# EIT_sample_circuit.net
KiCad netlist of a schematic drawn in EAGLE
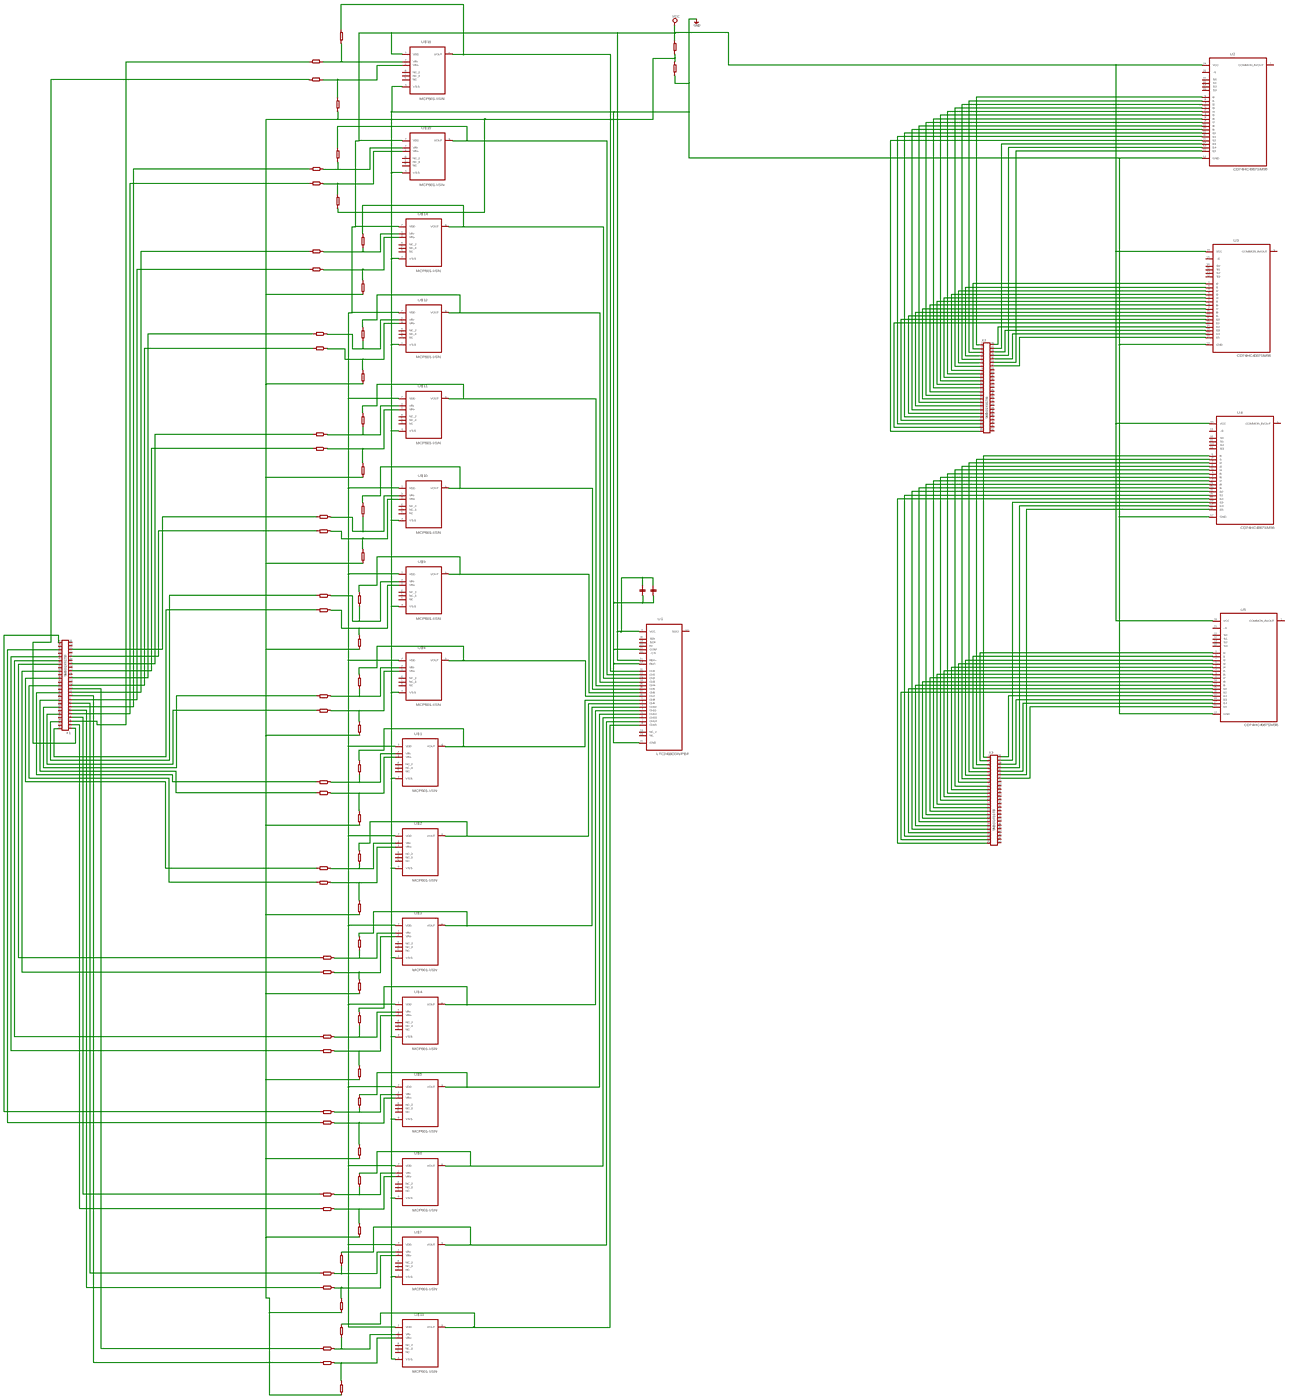
[diagram p0: schematic, sheet 1, overview]
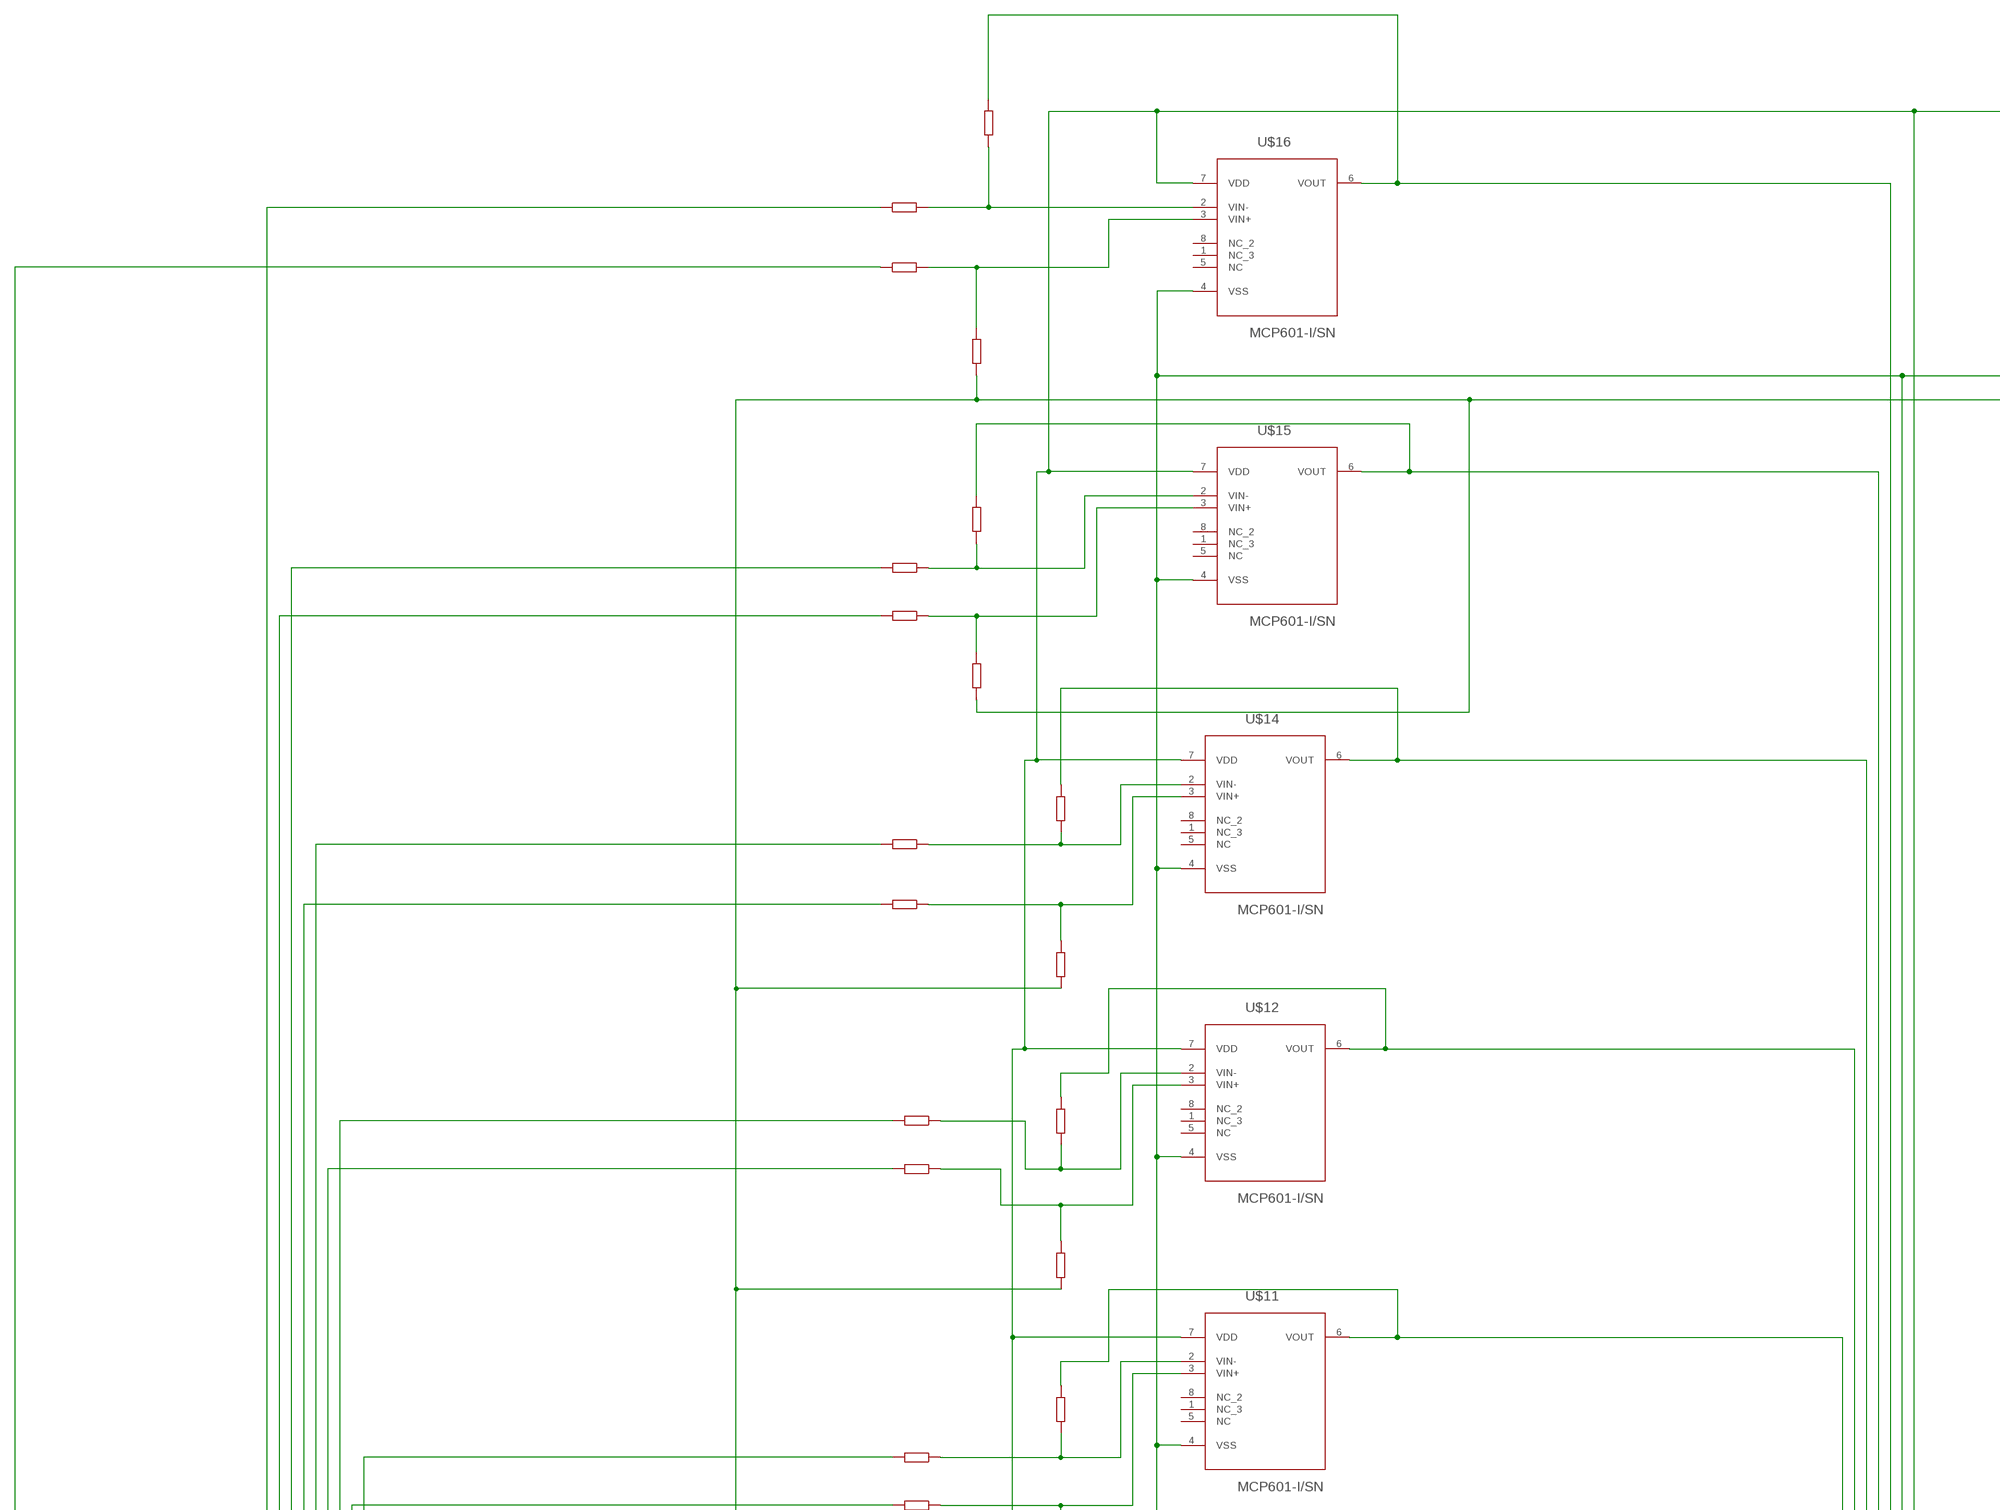
[diagram p1: schematic, sheet 1, part 1 of 5]
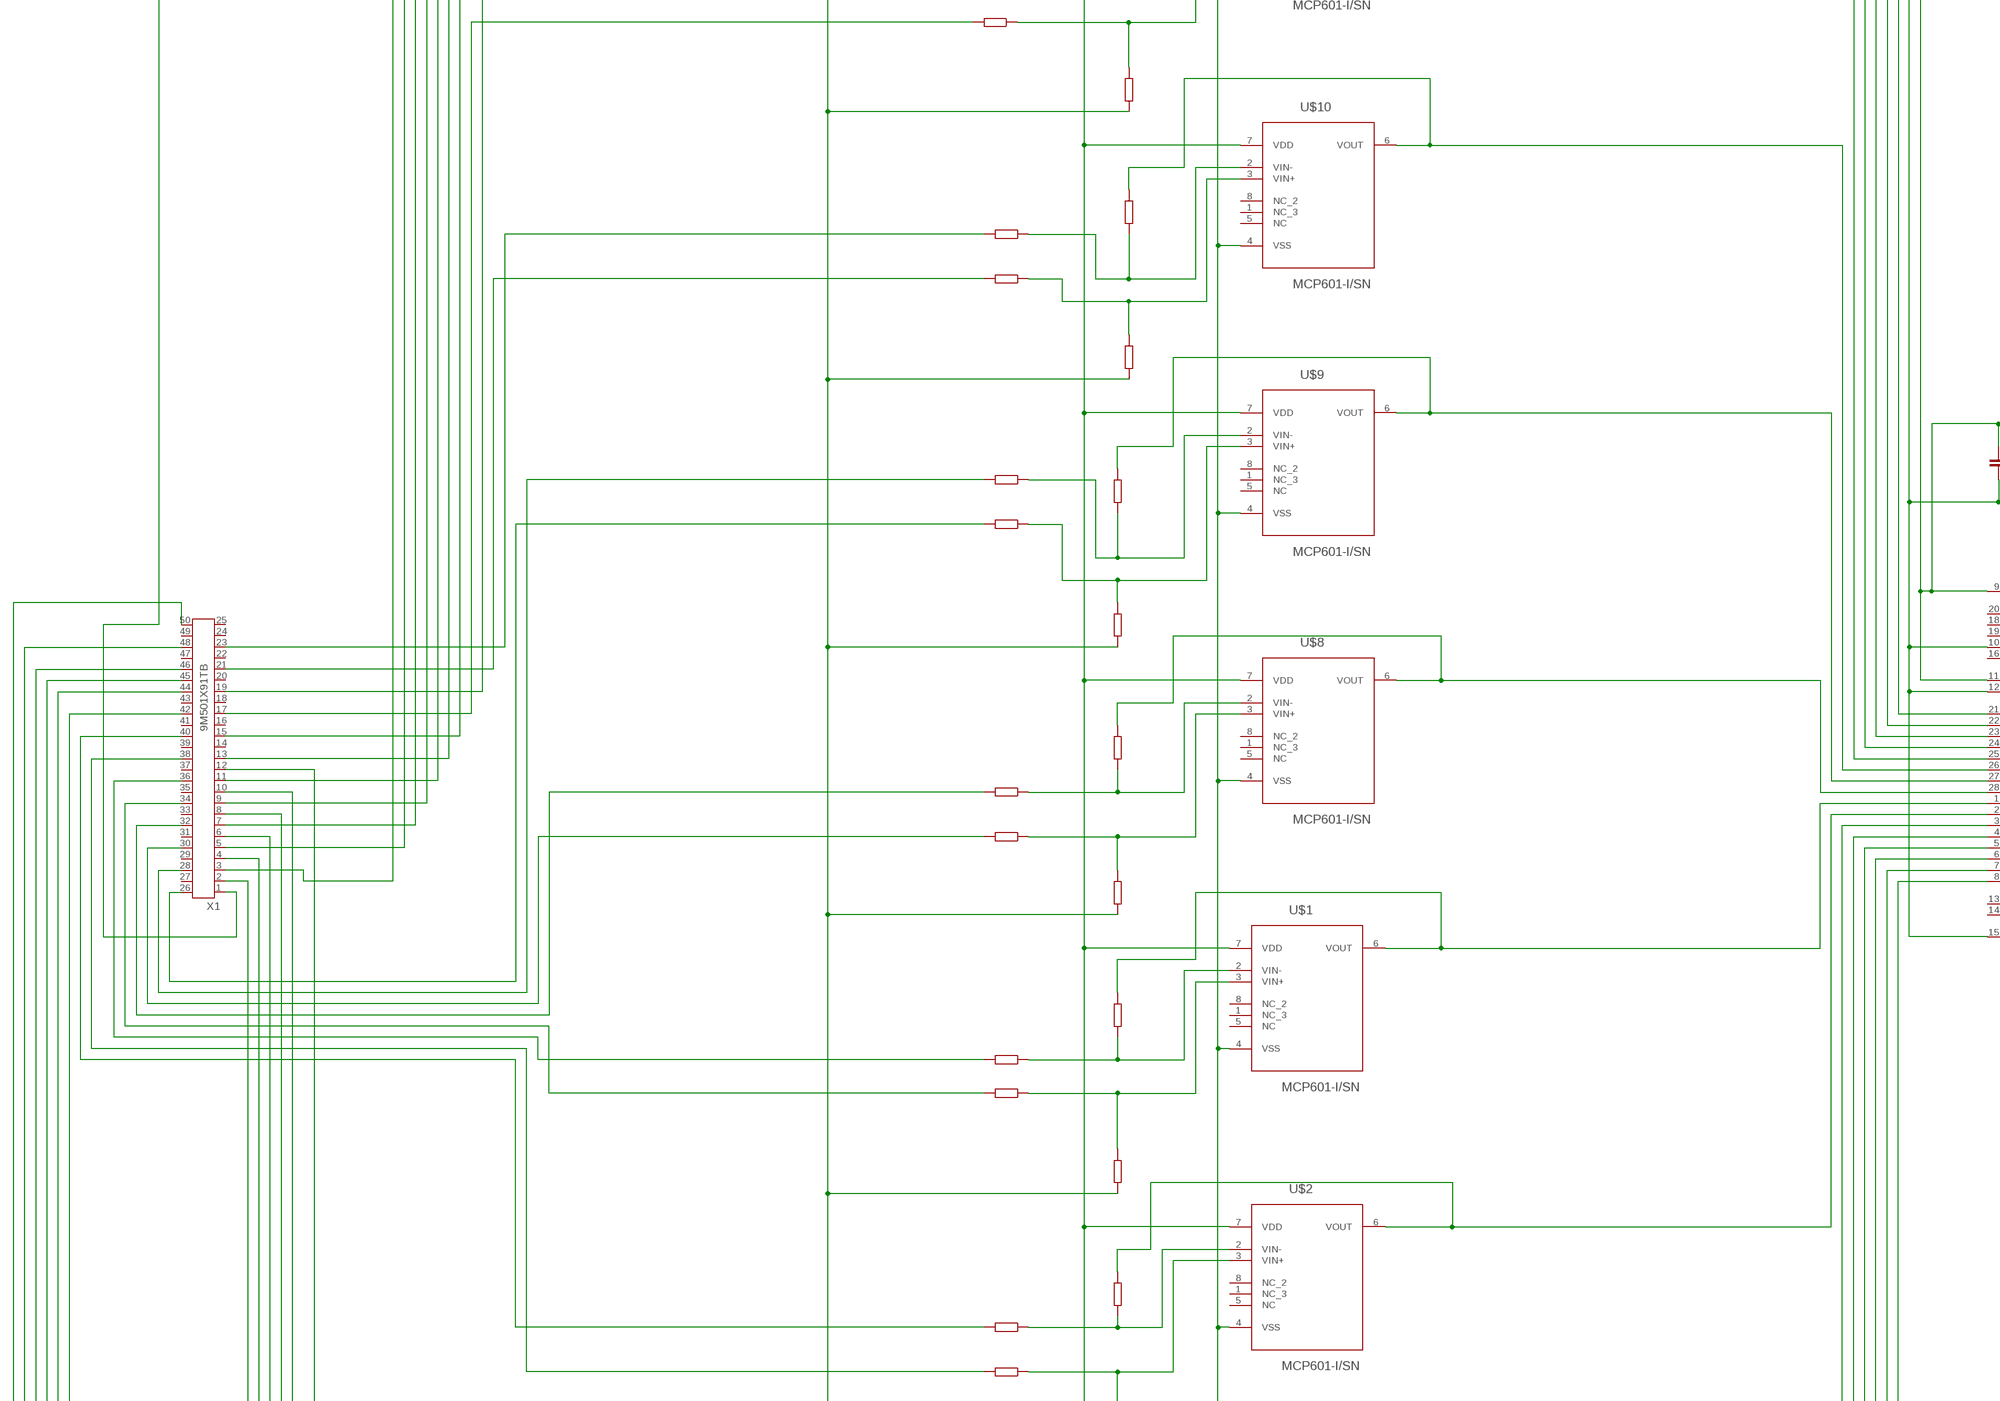
[diagram p2: schematic, sheet 1, part 2 of 5]
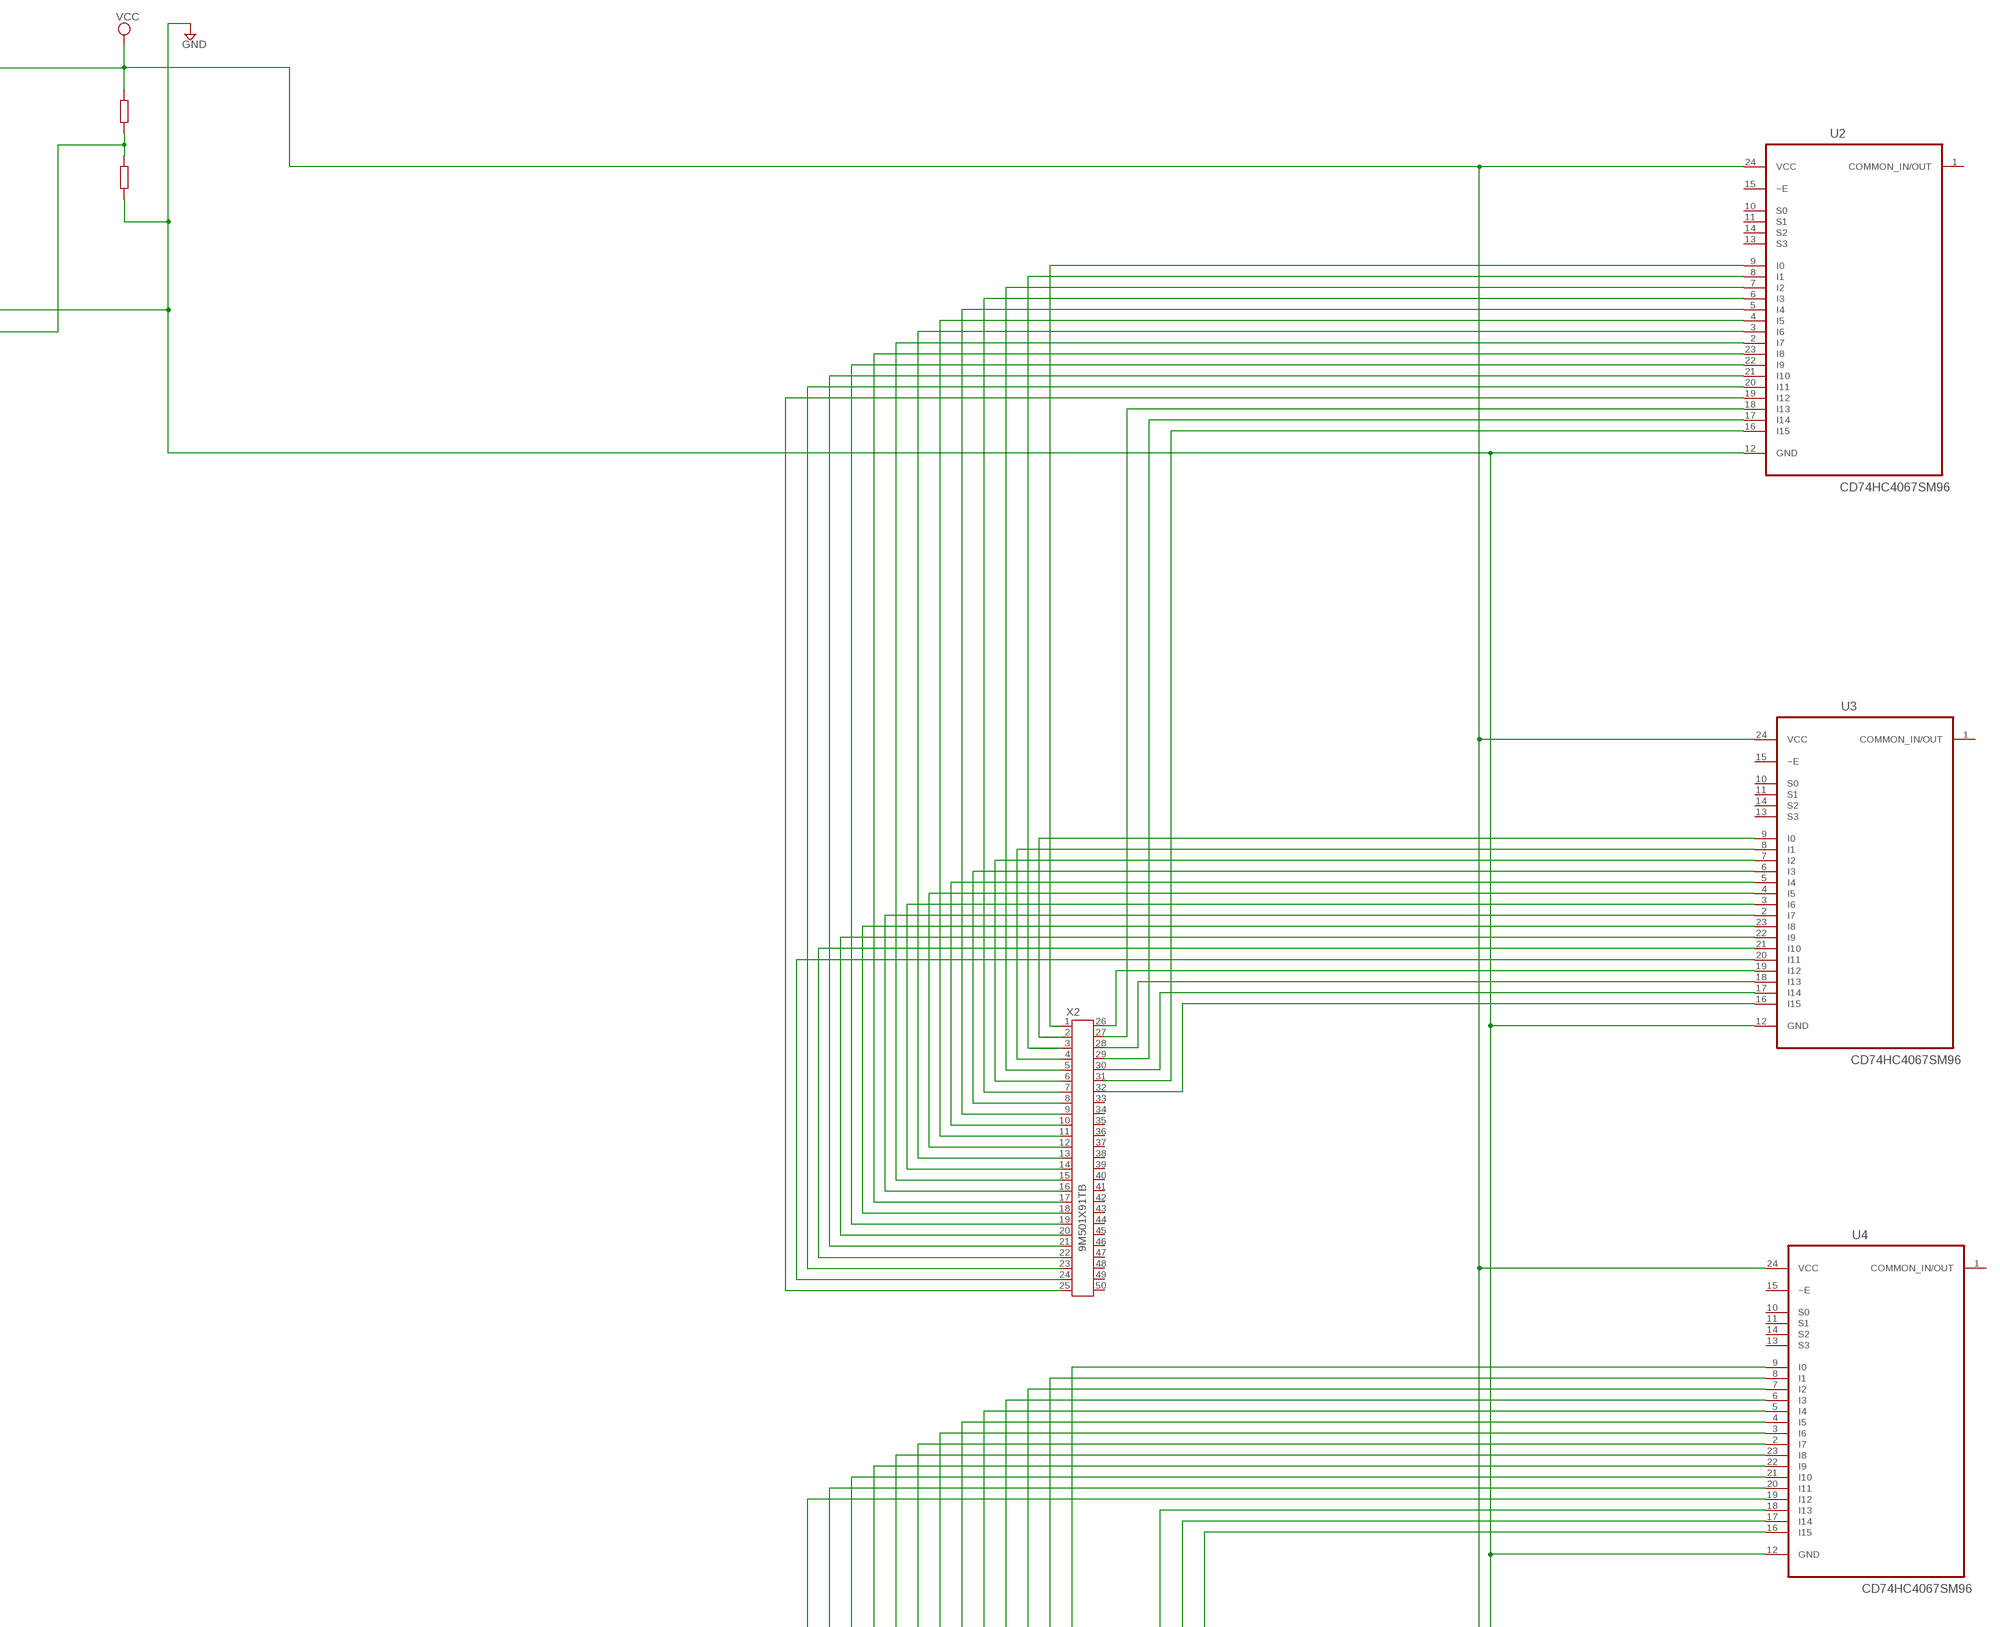
[diagram p3: schematic, sheet 1, part 3 of 5]
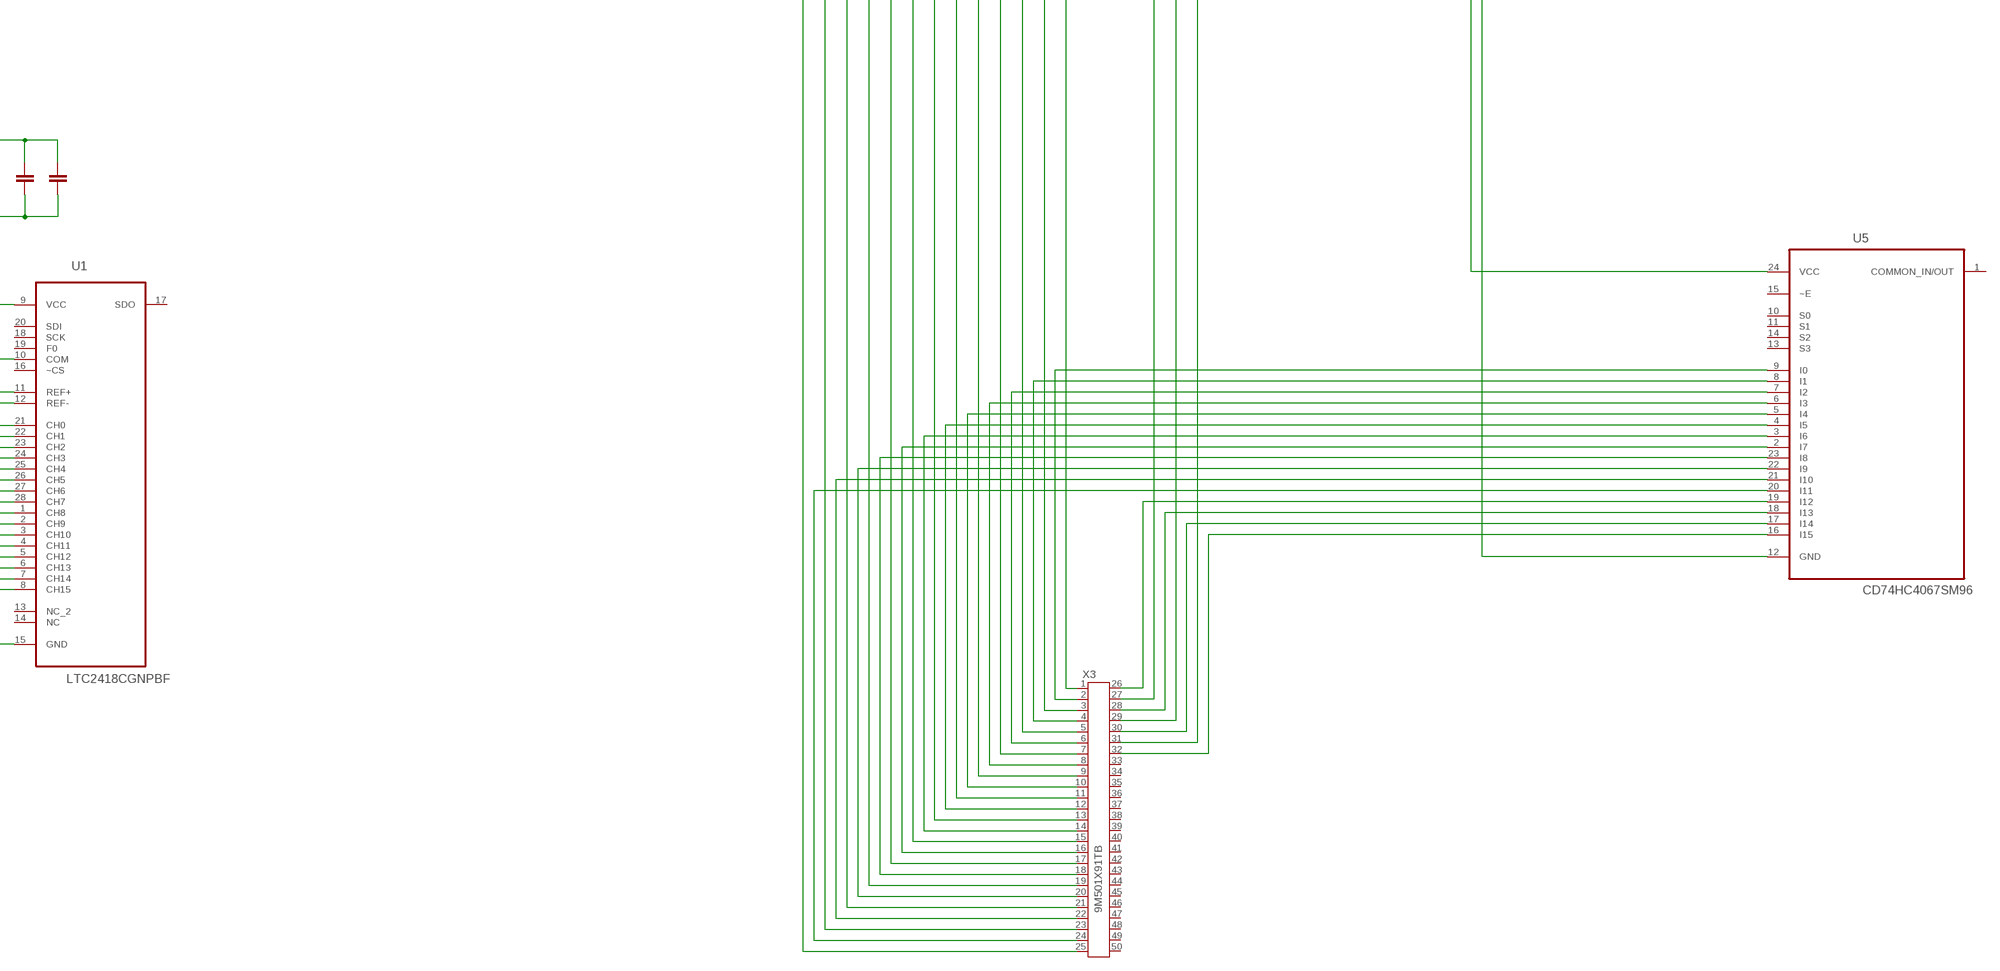
[diagram p4: schematic, sheet 1, part 4 of 5]
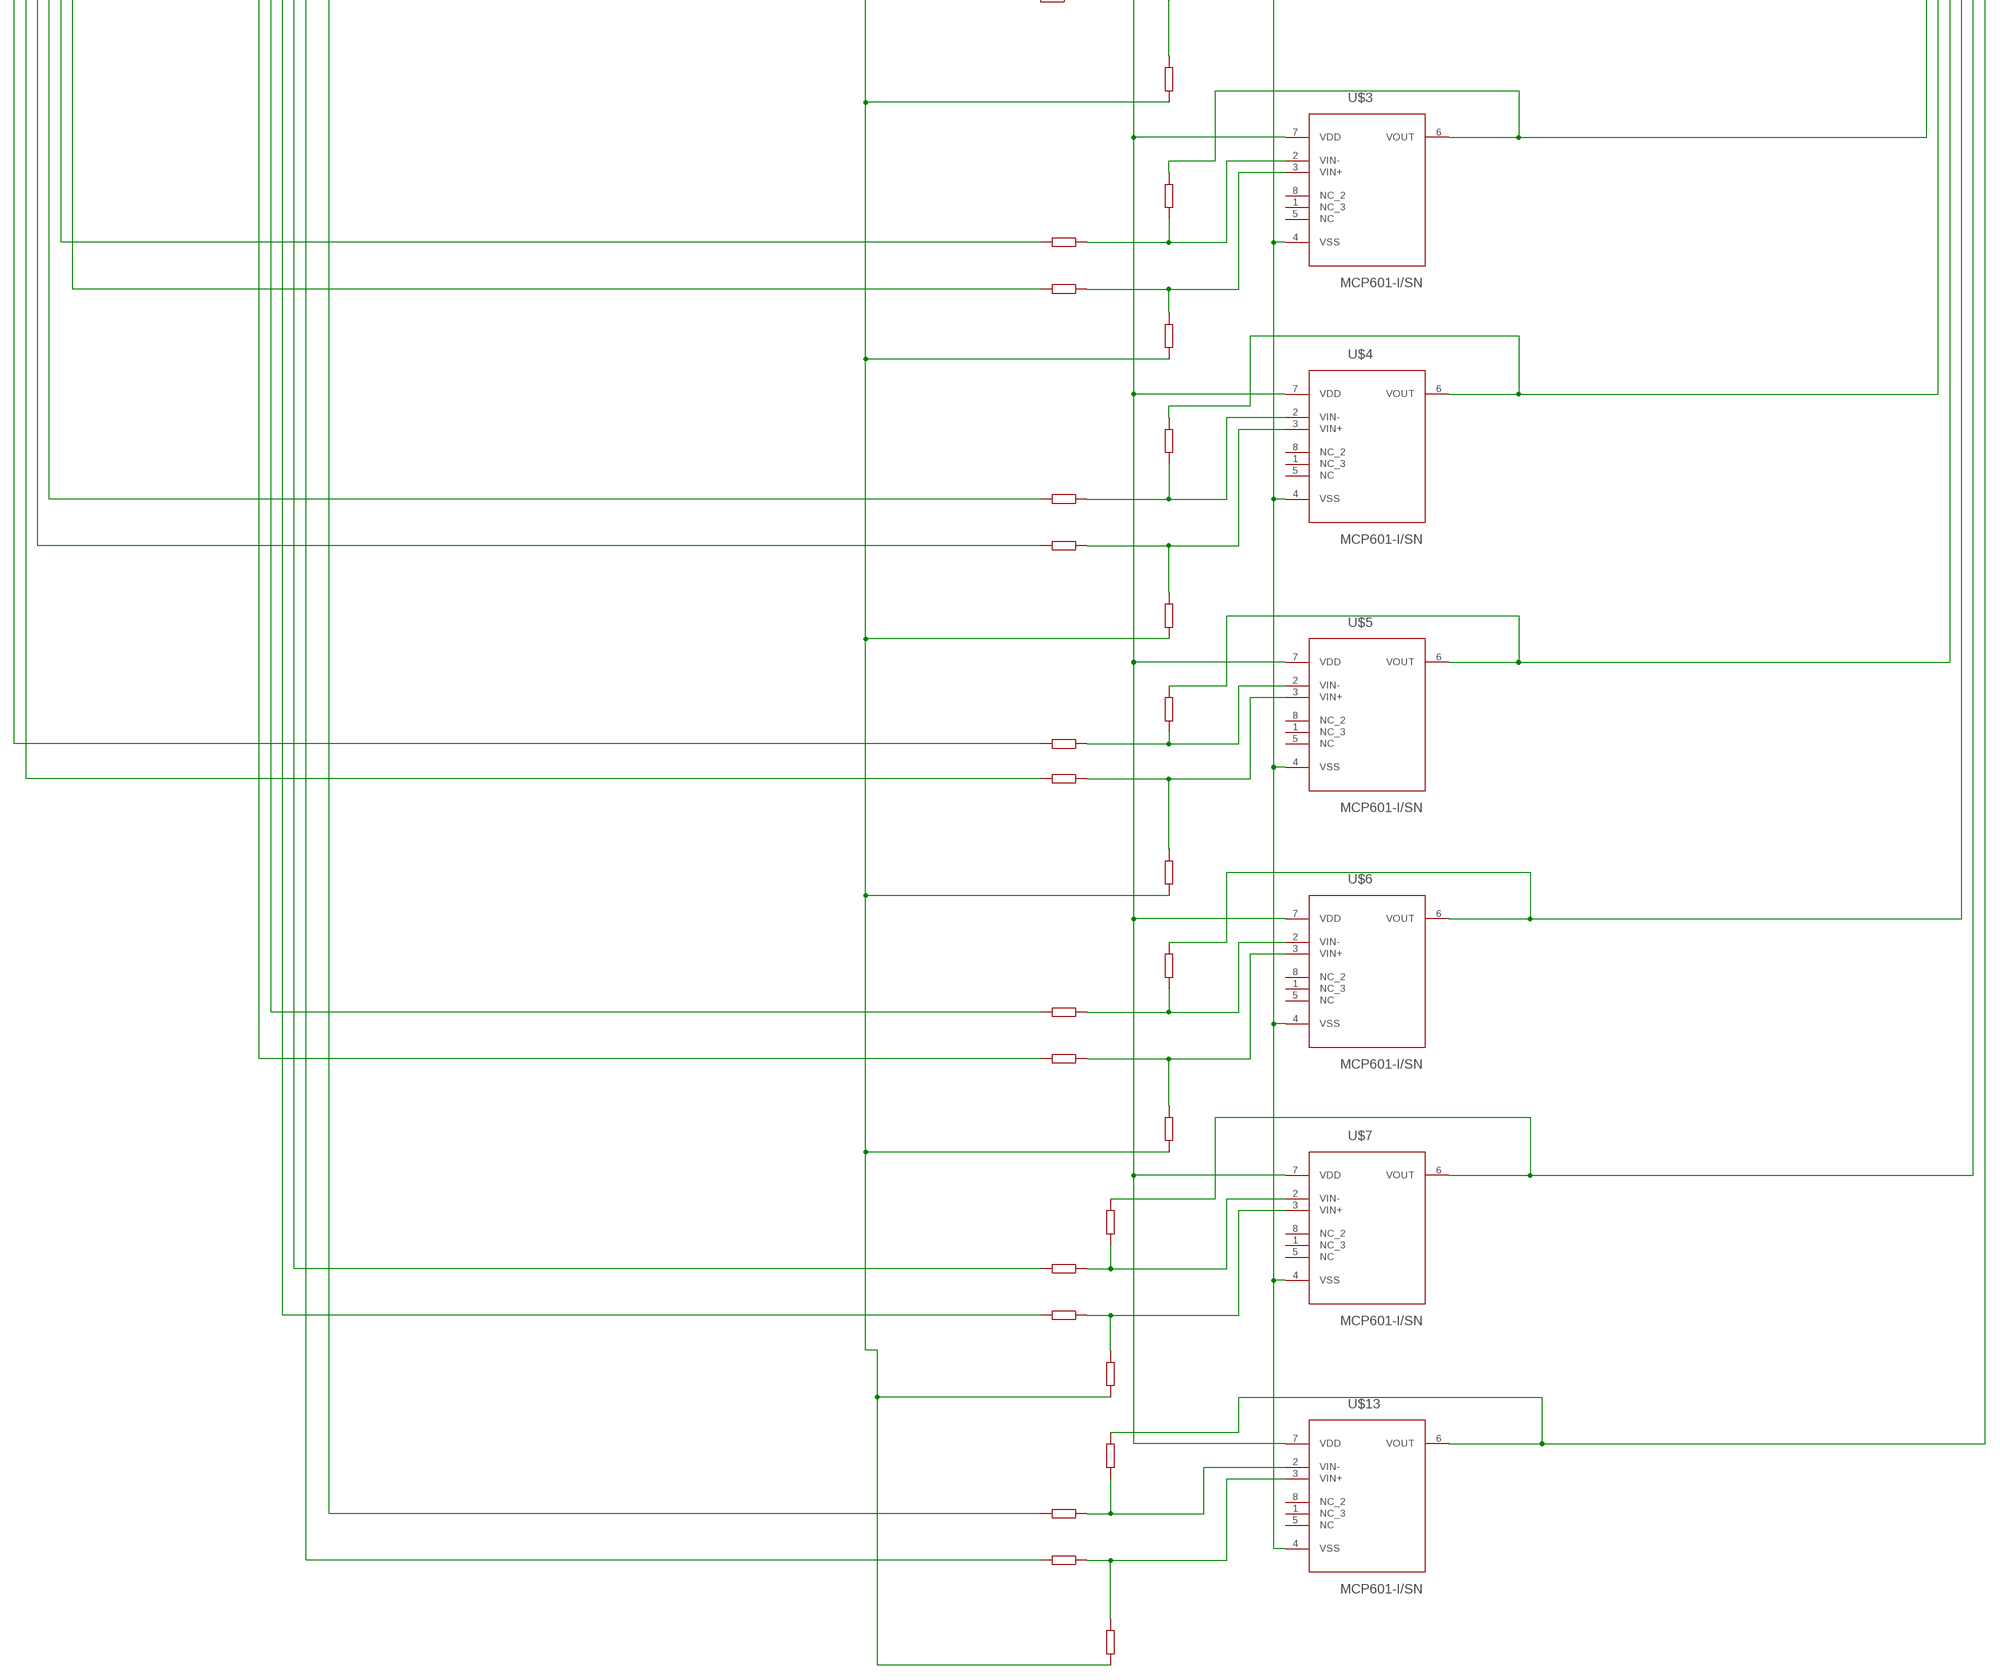
[diagram p5: schematic, sheet 1, part 5 of 5]

(export (version "E")
  (design (tool "Eeschema 10.0.6"))
  (components
    (comp (ref "U$1")
      (value "MCP601-I/SN")
      (footprint "eagle-import:SOIC127P600X175-8N")
      (libsource (lib "eagle-import") (part "MCP601-I/SN"))
    )
    (comp (ref "U$2")
      (value "MCP601-I/SN")
      (footprint "eagle-import:SOIC127P600X175-8N")
      (libsource (lib "eagle-import") (part "MCP601-I/SN"))
    )
    (comp (ref "U$3")
      (value "MCP601-I/SN")
      (footprint "eagle-import:SOIC127P600X175-8N")
      (libsource (lib "eagle-import") (part "MCP601-I/SN"))
    )
    (comp (ref "U$4")
      (value "MCP601-I/SN")
      (footprint "eagle-import:SOIC127P600X175-8N")
      (libsource (lib "eagle-import") (part "MCP601-I/SN"))
    )
    (comp (ref "U$5")
      (value "MCP601-I/SN")
      (footprint "eagle-import:SOIC127P600X175-8N")
      (libsource (lib "eagle-import") (part "MCP601-I/SN"))
    )
    (comp (ref "U$6")
      (value "MCP601-I/SN")
      (footprint "eagle-import:SOIC127P600X175-8N")
      (libsource (lib "eagle-import") (part "MCP601-I/SN"))
    )
    (comp (ref "U$7")
      (value "MCP601-I/SN")
      (footprint "eagle-import:SOIC127P600X175-8N")
      (libsource (lib "eagle-import") (part "MCP601-I/SN"))
    )
    (comp (ref "U$8")
      (value "MCP601-I/SN")
      (footprint "eagle-import:SOIC127P600X175-8N")
      (libsource (lib "eagle-import") (part "MCP601-I/SN"))
    )
    (comp (ref "U$9")
      (value "MCP601-I/SN")
      (footprint "eagle-import:SOIC127P600X175-8N")
      (libsource (lib "eagle-import") (part "MCP601-I/SN"))
    )
    (comp (ref "U$10")
      (value "MCP601-I/SN")
      (footprint "eagle-import:SOIC127P600X175-8N")
      (libsource (lib "eagle-import") (part "MCP601-I/SN"))
    )
    (comp (ref "U$11")
      (value "MCP601-I/SN")
      (footprint "eagle-import:SOIC127P600X175-8N")
      (libsource (lib "eagle-import") (part "MCP601-I/SN"))
    )
    (comp (ref "U$12")
      (value "MCP601-I/SN")
      (footprint "eagle-import:SOIC127P600X175-8N")
      (libsource (lib "eagle-import") (part "MCP601-I/SN"))
    )
    (comp (ref "U$13")
      (value "MCP601-I/SN")
      (footprint "eagle-import:SOIC127P600X175-8N")
      (libsource (lib "eagle-import") (part "MCP601-I/SN"))
    )
    (comp (ref "U$14")
      (value "MCP601-I/SN")
      (footprint "eagle-import:SOIC127P600X175-8N")
      (libsource (lib "eagle-import") (part "MCP601-I/SN"))
    )
    (comp (ref "U$15")
      (value "MCP601-I/SN")
      (footprint "eagle-import:SOIC127P600X175-8N")
      (libsource (lib "eagle-import") (part "MCP601-I/SN"))
    )
    (comp (ref "U$16")
      (value "MCP601-I/SN")
      (footprint "eagle-import:SOIC127P600X175-8N")
      (libsource (lib "eagle-import") (part "MCP601-I/SN"))
    )
    (comp (ref "U1")
      (value "LTC2418CGNPBF")
      (footprint "eagle-import:SOP63P600X175-28N")
      (fields (field (name "MPN") "LTC2418CGN#PBF"))
      (libsource (lib "eagle-import") (part "LTC2418CGNPBF"))
    )
    (comp (ref "U2")
      (value "CD74HC4067SM96")
      (footprint "eagle-import:SOP65P780X200-24N")
      (libsource (lib "eagle-import") (part "CD74HC4067SM96"))
    )
    (comp (ref "U3")
      (value "CD74HC4067SM96")
      (footprint "eagle-import:SOP65P780X200-24N")
      (libsource (lib "eagle-import") (part "CD74HC4067SM96"))
    )
    (comp (ref "U4")
      (value "CD74HC4067SM96")
      (footprint "eagle-import:SOP65P780X200-24N")
      (libsource (lib "eagle-import") (part "CD74HC4067SM96"))
    )
    (comp (ref "U5")
      (value "CD74HC4067SM96")
      (footprint "eagle-import:SOP65P780X200-24N")
      (libsource (lib "eagle-import") (part "CD74HC4067SM96"))
    )
    (comp (ref "X1")
      (value "9M501X91TB")
      (footprint "eagle-import:9M501X91")
      (libsource (lib "eagle-import") (part "9M501X91TB"))
    )
    (comp (ref "X2")
      (value "9M501X91TB")
      (footprint "eagle-import:9M501X91")
      (libsource (lib "eagle-import") (part "9M501X91TB"))
    )
    (comp (ref "X3")
      (value "9M501X91TB")
      (footprint "eagle-import:9M501X91")
      (libsource (lib "eagle-import") (part "9M501X91TB"))
    )
  )
  (nets
    (net (code "1") (name "GND") (class "Default")
      (node (ref "U$1") (pin "4") (pinfunction "VSS_4") (pintype "power_in"))
      (node (ref "U$10") (pin "4") (pinfunction "VSS_4") (pintype "power_in"))
      (node (ref "U$11") (pin "4") (pinfunction "VSS_4") (pintype "power_in"))
      (node (ref "U$12") (pin "4") (pinfunction "VSS_4") (pintype "power_in"))
      (node (ref "U$13") (pin "4") (pinfunction "VSS_4") (pintype "power_in"))
      (node (ref "U$14") (pin "4") (pinfunction "VSS_4") (pintype "power_in"))
      (node (ref "U$15") (pin "4") (pinfunction "VSS_4") (pintype "power_in"))
      (node (ref "U$16") (pin "4") (pinfunction "VSS_4") (pintype "power_in"))
      (node (ref "U$2") (pin "4") (pinfunction "VSS_4") (pintype "power_in"))
      (node (ref "U$3") (pin "4") (pinfunction "VSS_4") (pintype "power_in"))
      (node (ref "U$4") (pin "4") (pinfunction "VSS_4") (pintype "power_in"))
      (node (ref "U$5") (pin "4") (pinfunction "VSS_4") (pintype "power_in"))
      (node (ref "U$6") (pin "4") (pinfunction "VSS_4") (pintype "power_in"))
      (node (ref "U$7") (pin "4") (pinfunction "VSS_4") (pintype "power_in"))
      (node (ref "U$8") (pin "4") (pinfunction "VSS_4") (pintype "power_in"))
      (node (ref "U$9") (pin "4") (pinfunction "VSS_4") (pintype "power_in"))
      (node (ref "U1") (pin "10") (pinfunction "COM_10") (pintype "input"))
      (node (ref "U1") (pin "12") (pinfunction "REF-_12") (pintype "input"))
      (node (ref "U1") (pin "15") (pinfunction "GND_15") (pintype "passive"))
      (node (ref "U2") (pin "12") (pinfunction "GND_12") (pintype "passive"))
      (node (ref "U3") (pin "12") (pinfunction "GND_12") (pintype "passive"))
      (node (ref "U4") (pin "12") (pinfunction "GND_12") (pintype "passive"))
      (node (ref "U5") (pin "12") (pinfunction "GND_12") (pintype "passive"))
    )
    (net (code "2") (name "Net-(U$1-VOUT)") (class "Default")
      (node (ref "U$1") (pin "6") (pinfunction "VOUT_6") (pintype "output"))
      (node (ref "U1") (pin "1") (pinfunction "CH8_1") (pintype "input"))
    )
    (net (code "3") (name "Net-(U$2-VOUT)") (class "Default")
      (node (ref "U$2") (pin "6") (pinfunction "VOUT_6") (pintype "output"))
      (node (ref "U1") (pin "2") (pinfunction "CH9_2") (pintype "input"))
    )
    (net (code "4") (name "Net-(U$3-VOUT)") (class "Default")
      (node (ref "U$3") (pin "6") (pinfunction "VOUT_6") (pintype "output"))
      (node (ref "U1") (pin "3") (pinfunction "CH10_3") (pintype "input"))
    )
    (net (code "5") (name "Net-(U$4-VOUT)") (class "Default")
      (node (ref "U$4") (pin "6") (pinfunction "VOUT_6") (pintype "output"))
      (node (ref "U1") (pin "4") (pinfunction "CH11_4") (pintype "input"))
    )
    (net (code "6") (name "Net-(U$5-VOUT)") (class "Default")
      (node (ref "U$5") (pin "6") (pinfunction "VOUT_6") (pintype "output"))
      (node (ref "U1") (pin "5") (pinfunction "CH12_5") (pintype "input"))
    )
    (net (code "7") (name "Net-(U$6-VOUT)") (class "Default")
      (node (ref "U$6") (pin "6") (pinfunction "VOUT_6") (pintype "output"))
      (node (ref "U1") (pin "6") (pinfunction "CH13_6") (pintype "input"))
    )
    (net (code "8") (name "Net-(U$7-VOUT)") (class "Default")
      (node (ref "U$7") (pin "6") (pinfunction "VOUT_6") (pintype "output"))
      (node (ref "U1") (pin "7") (pinfunction "CH14_7") (pintype "input"))
    )
    (net (code "9") (name "Net-(U$8-VOUT)") (class "Default")
      (node (ref "U$8") (pin "6") (pinfunction "VOUT_6") (pintype "output"))
      (node (ref "U1") (pin "28") (pinfunction "CH7_28") (pintype "input"))
    )
    (net (code "10") (name "Net-(U$9-VOUT)") (class "Default")
      (node (ref "U$9") (pin "6") (pinfunction "VOUT_6") (pintype "output"))
      (node (ref "U1") (pin "27") (pinfunction "CH6_27") (pintype "input"))
    )
    (net (code "11") (name "Net-(U$10-VOUT)") (class "Default")
      (node (ref "U$10") (pin "6") (pinfunction "VOUT_6") (pintype "output"))
      (node (ref "U1") (pin "26") (pinfunction "CH5_26") (pintype "input"))
    )
    (net (code "12") (name "Net-(U$11-VOUT)") (class "Default")
      (node (ref "U$11") (pin "6") (pinfunction "VOUT_6") (pintype "output"))
      (node (ref "U1") (pin "25") (pinfunction "CH4_25") (pintype "input"))
    )
    (net (code "13") (name "Net-(U$12-VOUT)") (class "Default")
      (node (ref "U$12") (pin "6") (pinfunction "VOUT_6") (pintype "output"))
      (node (ref "U1") (pin "24") (pinfunction "CH3_24") (pintype "input"))
    )
    (net (code "14") (name "Net-(U$13-VOUT)") (class "Default")
      (node (ref "U$13") (pin "6") (pinfunction "VOUT_6") (pintype "output"))
      (node (ref "U1") (pin "8") (pinfunction "CH15_8") (pintype "input"))
    )
    (net (code "15") (name "Net-(U$14-VOUT)") (class "Default")
      (node (ref "U$14") (pin "6") (pinfunction "VOUT_6") (pintype "output"))
      (node (ref "U1") (pin "23") (pinfunction "CH2_23") (pintype "input"))
    )
    (net (code "16") (name "Net-(U$15-VOUT)") (class "Default")
      (node (ref "U$15") (pin "6") (pinfunction "VOUT_6") (pintype "output"))
      (node (ref "U1") (pin "22") (pinfunction "CH1_22") (pintype "input"))
    )
    (net (code "17") (name "Net-(U$16-VOUT)") (class "Default")
      (node (ref "U$16") (pin "6") (pinfunction "VOUT_6") (pintype "output"))
      (node (ref "U1") (pin "21") (pinfunction "CH0_21") (pintype "input"))
    )
    (net (code "18") (name "Net-(U2-I0)") (class "Default")
      (node (ref "U2") (pin "9") (pinfunction "I0_9") (pintype "input"))
      (node (ref "X2") (pin "1") (pinfunction "1_1") (pintype "passive"))
    )
    (net (code "19") (name "Net-(U2-I1)") (class "Default")
      (node (ref "U2") (pin "8") (pinfunction "I1_8") (pintype "input"))
      (node (ref "X2") (pin "3") (pinfunction "3_3") (pintype "passive"))
    )
    (net (code "20") (name "Net-(U2-I2)") (class "Default")
      (node (ref "U2") (pin "7") (pinfunction "I2_7") (pintype "input"))
      (node (ref "X2") (pin "5") (pinfunction "5_5") (pintype "passive"))
    )
    (net (code "21") (name "Net-(U2-I3)") (class "Default")
      (node (ref "U2") (pin "6") (pinfunction "I3_6") (pintype "input"))
      (node (ref "X2") (pin "7") (pinfunction "7_7") (pintype "passive"))
    )
    (net (code "22") (name "Net-(U2-I4)") (class "Default")
      (node (ref "U2") (pin "5") (pinfunction "I4_5") (pintype "input"))
      (node (ref "X2") (pin "9") (pinfunction "9_9") (pintype "passive"))
    )
    (net (code "23") (name "Net-(U2-I5)") (class "Default")
      (node (ref "U2") (pin "4") (pinfunction "I5_4") (pintype "input"))
      (node (ref "X2") (pin "11") (pinfunction "11_11") (pintype "passive"))
    )
    (net (code "24") (name "Net-(U2-I6)") (class "Default")
      (node (ref "U2") (pin "3") (pinfunction "I6_3") (pintype "input"))
      (node (ref "X2") (pin "13") (pinfunction "13_13") (pintype "passive"))
    )
    (net (code "25") (name "Net-(U2-I7)") (class "Default")
      (node (ref "U2") (pin "2") (pinfunction "I7_2") (pintype "input"))
      (node (ref "X2") (pin "15") (pinfunction "15_15") (pintype "passive"))
    )
    (net (code "26") (name "Net-(U2-I8)") (class "Default")
      (node (ref "U2") (pin "23") (pinfunction "I8_23") (pintype "input"))
      (node (ref "X2") (pin "17") (pinfunction "17_17") (pintype "passive"))
    )
    (net (code "27") (name "Net-(U2-I9)") (class "Default")
      (node (ref "U2") (pin "22") (pinfunction "I9_22") (pintype "input"))
      (node (ref "X2") (pin "19") (pinfunction "19_19") (pintype "passive"))
    )
    (net (code "28") (name "Net-(U2-I10)") (class "Default")
      (node (ref "U2") (pin "21") (pinfunction "I10_21") (pintype "input"))
      (node (ref "X2") (pin "21") (pinfunction "21_21") (pintype "passive"))
    )
    (net (code "29") (name "Net-(U2-I11)") (class "Default")
      (node (ref "U2") (pin "20") (pinfunction "I11_20") (pintype "input"))
      (node (ref "X2") (pin "23") (pinfunction "23_23") (pintype "passive"))
    )
    (net (code "30") (name "Net-(U2-I12)") (class "Default")
      (node (ref "U2") (pin "19") (pinfunction "I12_19") (pintype "input"))
      (node (ref "X2") (pin "25") (pinfunction "25_25") (pintype "passive"))
    )
    (net (code "31") (name "Net-(U2-I13)") (class "Default")
      (node (ref "U2") (pin "18") (pinfunction "I13_18") (pintype "input"))
      (node (ref "X2") (pin "27") (pinfunction "27_27") (pintype "passive"))
    )
    (net (code "32") (name "Net-(U2-I14)") (class "Default")
      (node (ref "U2") (pin "17") (pinfunction "I14_17") (pintype "input"))
      (node (ref "X2") (pin "29") (pinfunction "29_29") (pintype "passive"))
    )
    (net (code "33") (name "Net-(U2-I15)") (class "Default")
      (node (ref "U2") (pin "16") (pinfunction "I15_16") (pintype "input"))
      (node (ref "X2") (pin "31") (pinfunction "31_31") (pintype "passive"))
    )
    (net (code "34") (name "Net-(U3-I0)") (class "Default")
      (node (ref "U3") (pin "9") (pinfunction "I0_9") (pintype "input"))
      (node (ref "X2") (pin "2") (pinfunction "2_2") (pintype "passive"))
    )
    (net (code "35") (name "Net-(U3-I1)") (class "Default")
      (node (ref "U3") (pin "8") (pinfunction "I1_8") (pintype "input"))
      (node (ref "X2") (pin "4") (pinfunction "4_4") (pintype "passive"))
    )
    (net (code "36") (name "Net-(U3-I2)") (class "Default")
      (node (ref "U3") (pin "7") (pinfunction "I2_7") (pintype "input"))
      (node (ref "X2") (pin "6") (pinfunction "6_6") (pintype "passive"))
    )
    (net (code "37") (name "Net-(U3-I3)") (class "Default")
      (node (ref "U3") (pin "6") (pinfunction "I3_6") (pintype "input"))
      (node (ref "X2") (pin "8") (pinfunction "8_8") (pintype "passive"))
    )
    (net (code "38") (name "Net-(U3-I4)") (class "Default")
      (node (ref "U3") (pin "5") (pinfunction "I4_5") (pintype "input"))
      (node (ref "X2") (pin "10") (pinfunction "10_10") (pintype "passive"))
    )
    (net (code "39") (name "Net-(U3-I5)") (class "Default")
      (node (ref "U3") (pin "4") (pinfunction "I5_4") (pintype "input"))
      (node (ref "X2") (pin "12") (pinfunction "12_12") (pintype "passive"))
    )
    (net (code "40") (name "Net-(U3-I6)") (class "Default")
      (node (ref "U3") (pin "3") (pinfunction "I6_3") (pintype "input"))
      (node (ref "X2") (pin "14") (pinfunction "14_14") (pintype "passive"))
    )
    (net (code "41") (name "Net-(U3-I7)") (class "Default")
      (node (ref "U3") (pin "2") (pinfunction "I7_2") (pintype "input"))
      (node (ref "X2") (pin "16") (pinfunction "16_16") (pintype "passive"))
    )
    (net (code "42") (name "Net-(U3-I8)") (class "Default")
      (node (ref "U3") (pin "23") (pinfunction "I8_23") (pintype "input"))
      (node (ref "X2") (pin "18") (pinfunction "18_18") (pintype "passive"))
    )
    (net (code "43") (name "Net-(U3-I9)") (class "Default")
      (node (ref "U3") (pin "22") (pinfunction "I9_22") (pintype "input"))
      (node (ref "X2") (pin "20") (pinfunction "20_20") (pintype "passive"))
    )
    (net (code "44") (name "Net-(U3-I10)") (class "Default")
      (node (ref "U3") (pin "21") (pinfunction "I10_21") (pintype "input"))
      (node (ref "X2") (pin "22") (pinfunction "22_22") (pintype "passive"))
    )
    (net (code "45") (name "Net-(U3-I11)") (class "Default")
      (node (ref "U3") (pin "20") (pinfunction "I11_20") (pintype "input"))
      (node (ref "X2") (pin "24") (pinfunction "24_24") (pintype "passive"))
    )
    (net (code "46") (name "Net-(U3-I12)") (class "Default")
      (node (ref "U3") (pin "19") (pinfunction "I12_19") (pintype "input"))
      (node (ref "X2") (pin "26") (pinfunction "26_26") (pintype "passive"))
    )
    (net (code "47") (name "Net-(U3-I13)") (class "Default")
      (node (ref "U3") (pin "18") (pinfunction "I13_18") (pintype "input"))
      (node (ref "X2") (pin "28") (pinfunction "28_28") (pintype "passive"))
    )
    (net (code "48") (name "Net-(U3-I14)") (class "Default")
      (node (ref "U3") (pin "17") (pinfunction "I14_17") (pintype "input"))
      (node (ref "X2") (pin "30") (pinfunction "30_30") (pintype "passive"))
    )
    (net (code "49") (name "Net-(U3-I15)") (class "Default")
      (node (ref "U3") (pin "16") (pinfunction "I15_16") (pintype "input"))
      (node (ref "X2") (pin "32") (pinfunction "32_32") (pintype "passive"))
    )
    (net (code "50") (name "Net-(U4-I0)") (class "Default")
      (node (ref "U4") (pin "9") (pinfunction "I0_9") (pintype "input"))
      (node (ref "X3") (pin "1") (pinfunction "1_1") (pintype "passive"))
    )
    (net (code "51") (name "Net-(U4-I1)") (class "Default")
      (node (ref "U4") (pin "8") (pinfunction "I1_8") (pintype "input"))
      (node (ref "X3") (pin "3") (pinfunction "3_3") (pintype "passive"))
    )
    (net (code "52") (name "Net-(U4-I2)") (class "Default")
      (node (ref "U4") (pin "7") (pinfunction "I2_7") (pintype "input"))
      (node (ref "X3") (pin "5") (pinfunction "5_5") (pintype "passive"))
    )
    (net (code "53") (name "Net-(U4-I3)") (class "Default")
      (node (ref "U4") (pin "6") (pinfunction "I3_6") (pintype "input"))
      (node (ref "X3") (pin "7") (pinfunction "7_7") (pintype "passive"))
    )
    (net (code "54") (name "Net-(U4-I4)") (class "Default")
      (node (ref "U4") (pin "5") (pinfunction "I4_5") (pintype "input"))
      (node (ref "X3") (pin "9") (pinfunction "9_9") (pintype "passive"))
    )
    (net (code "55") (name "Net-(U4-I5)") (class "Default")
      (node (ref "U4") (pin "4") (pinfunction "I5_4") (pintype "input"))
      (node (ref "X3") (pin "11") (pinfunction "11_11") (pintype "passive"))
    )
    (net (code "56") (name "Net-(U4-I6)") (class "Default")
      (node (ref "U4") (pin "3") (pinfunction "I6_3") (pintype "input"))
      (node (ref "X3") (pin "13") (pinfunction "13_13") (pintype "passive"))
    )
    (net (code "57") (name "Net-(U4-I7)") (class "Default")
      (node (ref "U4") (pin "2") (pinfunction "I7_2") (pintype "input"))
      (node (ref "X3") (pin "15") (pinfunction "15_15") (pintype "passive"))
    )
    (net (code "58") (name "Net-(U4-I8)") (class "Default")
      (node (ref "U4") (pin "23") (pinfunction "I8_23") (pintype "input"))
      (node (ref "X3") (pin "17") (pinfunction "17_17") (pintype "passive"))
    )
    (net (code "59") (name "Net-(U4-I9)") (class "Default")
      (node (ref "U4") (pin "22") (pinfunction "I9_22") (pintype "input"))
      (node (ref "X3") (pin "19") (pinfunction "19_19") (pintype "passive"))
    )
    (net (code "60") (name "Net-(U4-I10)") (class "Default")
      (node (ref "U4") (pin "21") (pinfunction "I10_21") (pintype "input"))
      (node (ref "X3") (pin "21") (pinfunction "21_21") (pintype "passive"))
    )
    (net (code "61") (name "Net-(U4-I11)") (class "Default")
      (node (ref "U4") (pin "20") (pinfunction "I11_20") (pintype "input"))
      (node (ref "X3") (pin "23") (pinfunction "23_23") (pintype "passive"))
    )
    (net (code "62") (name "Net-(U4-I12)") (class "Default")
      (node (ref "U4") (pin "19") (pinfunction "I12_19") (pintype "input"))
      (node (ref "X3") (pin "25") (pinfunction "25_25") (pintype "passive"))
    )
    (net (code "63") (name "Net-(U4-I13)") (class "Default")
      (node (ref "U4") (pin "18") (pinfunction "I13_18") (pintype "input"))
      (node (ref "X3") (pin "27") (pinfunction "27_27") (pintype "passive"))
    )
    (net (code "64") (name "Net-(U4-I14)") (class "Default")
      (node (ref "U4") (pin "17") (pinfunction "I14_17") (pintype "input"))
      (node (ref "X3") (pin "29") (pinfunction "29_29") (pintype "passive"))
    )
    (net (code "65") (name "Net-(U4-I15)") (class "Default")
      (node (ref "U4") (pin "16") (pinfunction "I15_16") (pintype "input"))
      (node (ref "X3") (pin "31") (pinfunction "31_31") (pintype "passive"))
    )
    (net (code "66") (name "Net-(U5-I0)") (class "Default")
      (node (ref "U5") (pin "9") (pinfunction "I0_9") (pintype "input"))
      (node (ref "X3") (pin "2") (pinfunction "2_2") (pintype "passive"))
    )
    (net (code "67") (name "Net-(U5-I1)") (class "Default")
      (node (ref "U5") (pin "8") (pinfunction "I1_8") (pintype "input"))
      (node (ref "X3") (pin "4") (pinfunction "4_4") (pintype "passive"))
    )
    (net (code "68") (name "Net-(U5-I2)") (class "Default")
      (node (ref "U5") (pin "7") (pinfunction "I2_7") (pintype "input"))
      (node (ref "X3") (pin "6") (pinfunction "6_6") (pintype "passive"))
    )
    (net (code "69") (name "Net-(U5-I3)") (class "Default")
      (node (ref "U5") (pin "6") (pinfunction "I3_6") (pintype "input"))
      (node (ref "X3") (pin "8") (pinfunction "8_8") (pintype "passive"))
    )
    (net (code "70") (name "Net-(U5-I4)") (class "Default")
      (node (ref "U5") (pin "5") (pinfunction "I4_5") (pintype "input"))
      (node (ref "X3") (pin "10") (pinfunction "10_10") (pintype "passive"))
    )
    (net (code "71") (name "Net-(U5-I5)") (class "Default")
      (node (ref "U5") (pin "4") (pinfunction "I5_4") (pintype "input"))
      (node (ref "X3") (pin "12") (pinfunction "12_12") (pintype "passive"))
    )
    (net (code "72") (name "Net-(U5-I6)") (class "Default")
      (node (ref "U5") (pin "3") (pinfunction "I6_3") (pintype "input"))
      (node (ref "X3") (pin "14") (pinfunction "14_14") (pintype "passive"))
    )
    (net (code "73") (name "Net-(U5-I7)") (class "Default")
      (node (ref "U5") (pin "2") (pinfunction "I7_2") (pintype "input"))
      (node (ref "X3") (pin "16") (pinfunction "16_16") (pintype "passive"))
    )
    (net (code "74") (name "Net-(U5-I8)") (class "Default")
      (node (ref "U5") (pin "23") (pinfunction "I8_23") (pintype "input"))
      (node (ref "X3") (pin "18") (pinfunction "18_18") (pintype "passive"))
    )
    (net (code "75") (name "Net-(U5-I9)") (class "Default")
      (node (ref "U5") (pin "22") (pinfunction "I9_22") (pintype "input"))
      (node (ref "X3") (pin "20") (pinfunction "20_20") (pintype "passive"))
    )
    (net (code "76") (name "Net-(U5-I10)") (class "Default")
      (node (ref "U5") (pin "21") (pinfunction "I10_21") (pintype "input"))
      (node (ref "X3") (pin "22") (pinfunction "22_22") (pintype "passive"))
    )
    (net (code "77") (name "Net-(U5-I11)") (class "Default")
      (node (ref "U5") (pin "20") (pinfunction "I11_20") (pintype "input"))
      (node (ref "X3") (pin "24") (pinfunction "24_24") (pintype "passive"))
    )
    (net (code "78") (name "Net-(U5-I12)") (class "Default")
      (node (ref "U5") (pin "19") (pinfunction "I12_19") (pintype "input"))
      (node (ref "X3") (pin "26") (pinfunction "26_26") (pintype "passive"))
    )
    (net (code "79") (name "Net-(U5-I13)") (class "Default")
      (node (ref "U5") (pin "18") (pinfunction "I13_18") (pintype "input"))
      (node (ref "X3") (pin "28") (pinfunction "28_28") (pintype "passive"))
    )
    (net (code "80") (name "Net-(U5-I14)") (class "Default")
      (node (ref "U5") (pin "17") (pinfunction "I14_17") (pintype "input"))
      (node (ref "X3") (pin "30") (pinfunction "30_30") (pintype "passive"))
    )
    (net (code "81") (name "Net-(U5-I15)") (class "Default")
      (node (ref "U5") (pin "16") (pinfunction "I15_16") (pintype "input"))
      (node (ref "X3") (pin "32") (pinfunction "32_32") (pintype "passive"))
    )
    (net (code "82") (name "VCC") (class "Default")
      (node (ref "U$1") (pin "7") (pinfunction "VDD_7") (pintype "power_in"))
      (node (ref "U$10") (pin "7") (pinfunction "VDD_7") (pintype "power_in"))
      (node (ref "U$11") (pin "7") (pinfunction "VDD_7") (pintype "power_in"))
      (node (ref "U$12") (pin "7") (pinfunction "VDD_7") (pintype "power_in"))
      (node (ref "U$13") (pin "7") (pinfunction "VDD_7") (pintype "power_in"))
      (node (ref "U$14") (pin "7") (pinfunction "VDD_7") (pintype "power_in"))
      (node (ref "U$15") (pin "7") (pinfunction "VDD_7") (pintype "power_in"))
      (node (ref "U$16") (pin "7") (pinfunction "VDD_7") (pintype "power_in"))
      (node (ref "U$2") (pin "7") (pinfunction "VDD_7") (pintype "power_in"))
      (node (ref "U$3") (pin "7") (pinfunction "VDD_7") (pintype "power_in"))
      (node (ref "U$4") (pin "7") (pinfunction "VDD_7") (pintype "power_in"))
      (node (ref "U$5") (pin "7") (pinfunction "VDD_7") (pintype "power_in"))
      (node (ref "U$6") (pin "7") (pinfunction "VDD_7") (pintype "power_in"))
      (node (ref "U$7") (pin "7") (pinfunction "VDD_7") (pintype "power_in"))
      (node (ref "U$8") (pin "7") (pinfunction "VDD_7") (pintype "power_in"))
      (node (ref "U$9") (pin "7") (pinfunction "VDD_7") (pintype "power_in"))
      (node (ref "U1") (pin "11") (pinfunction "REF+_11") (pintype "input"))
      (node (ref "U1") (pin "9") (pinfunction "VCC_9") (pintype "power_in"))
      (node (ref "U2") (pin "24") (pinfunction "VCC_24") (pintype "power_in"))
      (node (ref "U3") (pin "24") (pinfunction "VCC_24") (pintype "power_in"))
      (node (ref "U4") (pin "24") (pinfunction "VCC_24") (pintype "power_in"))
      (node (ref "U5") (pin "24") (pinfunction "VCC_24") (pintype "power_in"))
    )
    (net (code "83") (name "unconnected-(U$1-NC-Pad5)") (class "Default")
      (node (ref "U$1") (pin "5") (pinfunction "NC_5") (pintype "no_connect"))
    )
    (net (code "84") (name "unconnected-(U$1-NC_2-Pad8)") (class "Default")
      (node (ref "U$1") (pin "8") (pinfunction "NC_2_8") (pintype "no_connect"))
    )
    (net (code "85") (name "unconnected-(U$1-NC_3-Pad1)") (class "Default")
      (node (ref "U$1") (pin "1") (pinfunction "NC_3_1") (pintype "no_connect"))
    )
    (net (code "86") (name "unconnected-(U$1-VIN+-Pad3)") (class "Default")
      (node (ref "U$1") (pin "3") (pinfunction "VIN+_3") (pintype "input"))
    )
    (net (code "87") (name "unconnected-(U$1-VIN--Pad2)") (class "Default")
      (node (ref "U$1") (pin "2") (pinfunction "VIN-_2") (pintype "input"))
    )
    (net (code "88") (name "unconnected-(U$2-NC-Pad5)") (class "Default")
      (node (ref "U$2") (pin "5") (pinfunction "NC_5") (pintype "no_connect"))
    )
    (net (code "89") (name "unconnected-(U$2-NC_2-Pad8)") (class "Default")
      (node (ref "U$2") (pin "8") (pinfunction "NC_2_8") (pintype "no_connect"))
    )
    (net (code "90") (name "unconnected-(U$2-NC_3-Pad1)") (class "Default")
      (node (ref "U$2") (pin "1") (pinfunction "NC_3_1") (pintype "no_connect"))
    )
    (net (code "91") (name "unconnected-(U$2-VIN+-Pad3)") (class "Default")
      (node (ref "U$2") (pin "3") (pinfunction "VIN+_3") (pintype "input"))
    )
    (net (code "92") (name "unconnected-(U$2-VIN--Pad2)") (class "Default")
      (node (ref "U$2") (pin "2") (pinfunction "VIN-_2") (pintype "input"))
    )
    (net (code "93") (name "unconnected-(U$3-NC-Pad5)") (class "Default")
      (node (ref "U$3") (pin "5") (pinfunction "NC_5") (pintype "no_connect"))
    )
    (net (code "94") (name "unconnected-(U$3-NC_2-Pad8)") (class "Default")
      (node (ref "U$3") (pin "8") (pinfunction "NC_2_8") (pintype "no_connect"))
    )
    (net (code "95") (name "unconnected-(U$3-NC_3-Pad1)") (class "Default")
      (node (ref "U$3") (pin "1") (pinfunction "NC_3_1") (pintype "no_connect"))
    )
    (net (code "96") (name "unconnected-(U$3-VIN+-Pad3)") (class "Default")
      (node (ref "U$3") (pin "3") (pinfunction "VIN+_3") (pintype "input"))
    )
    (net (code "97") (name "unconnected-(U$3-VIN--Pad2)") (class "Default")
      (node (ref "U$3") (pin "2") (pinfunction "VIN-_2") (pintype "input"))
    )
    (net (code "98") (name "unconnected-(U$4-NC-Pad5)") (class "Default")
      (node (ref "U$4") (pin "5") (pinfunction "NC_5") (pintype "no_connect"))
    )
    (net (code "99") (name "unconnected-(U$4-NC_2-Pad8)") (class "Default")
      (node (ref "U$4") (pin "8") (pinfunction "NC_2_8") (pintype "no_connect"))
    )
    (net (code "100") (name "unconnected-(U$4-NC_3-Pad1)") (class "Default")
      (node (ref "U$4") (pin "1") (pinfunction "NC_3_1") (pintype "no_connect"))
    )
    (net (code "101") (name "unconnected-(U$4-VIN+-Pad3)") (class "Default")
      (node (ref "U$4") (pin "3") (pinfunction "VIN+_3") (pintype "input"))
    )
    (net (code "102") (name "unconnected-(U$4-VIN--Pad2)") (class "Default")
      (node (ref "U$4") (pin "2") (pinfunction "VIN-_2") (pintype "input"))
    )
    (net (code "103") (name "unconnected-(U$5-NC-Pad5)") (class "Default")
      (node (ref "U$5") (pin "5") (pinfunction "NC_5") (pintype "no_connect"))
    )
    (net (code "104") (name "unconnected-(U$5-NC_2-Pad8)") (class "Default")
      (node (ref "U$5") (pin "8") (pinfunction "NC_2_8") (pintype "no_connect"))
    )
    (net (code "105") (name "unconnected-(U$5-NC_3-Pad1)") (class "Default")
      (node (ref "U$5") (pin "1") (pinfunction "NC_3_1") (pintype "no_connect"))
    )
    (net (code "106") (name "unconnected-(U$5-VIN+-Pad3)") (class "Default")
      (node (ref "U$5") (pin "3") (pinfunction "VIN+_3") (pintype "input"))
    )
    (net (code "107") (name "unconnected-(U$5-VIN--Pad2)") (class "Default")
      (node (ref "U$5") (pin "2") (pinfunction "VIN-_2") (pintype "input"))
    )
    (net (code "108") (name "unconnected-(U$6-NC-Pad5)") (class "Default")
      (node (ref "U$6") (pin "5") (pinfunction "NC_5") (pintype "no_connect"))
    )
    (net (code "109") (name "unconnected-(U$6-NC_2-Pad8)") (class "Default")
      (node (ref "U$6") (pin "8") (pinfunction "NC_2_8") (pintype "no_connect"))
    )
    (net (code "110") (name "unconnected-(U$6-NC_3-Pad1)") (class "Default")
      (node (ref "U$6") (pin "1") (pinfunction "NC_3_1") (pintype "no_connect"))
    )
    (net (code "111") (name "unconnected-(U$6-VIN+-Pad3)") (class "Default")
      (node (ref "U$6") (pin "3") (pinfunction "VIN+_3") (pintype "input"))
    )
    (net (code "112") (name "unconnected-(U$6-VIN--Pad2)") (class "Default")
      (node (ref "U$6") (pin "2") (pinfunction "VIN-_2") (pintype "input"))
    )
    (net (code "113") (name "unconnected-(U$7-NC-Pad5)") (class "Default")
      (node (ref "U$7") (pin "5") (pinfunction "NC_5") (pintype "no_connect"))
    )
    (net (code "114") (name "unconnected-(U$7-NC_2-Pad8)") (class "Default")
      (node (ref "U$7") (pin "8") (pinfunction "NC_2_8") (pintype "no_connect"))
    )
    (net (code "115") (name "unconnected-(U$7-NC_3-Pad1)") (class "Default")
      (node (ref "U$7") (pin "1") (pinfunction "NC_3_1") (pintype "no_connect"))
    )
    (net (code "116") (name "unconnected-(U$7-VIN+-Pad3)") (class "Default")
      (node (ref "U$7") (pin "3") (pinfunction "VIN+_3") (pintype "input"))
    )
    (net (code "117") (name "unconnected-(U$7-VIN--Pad2)") (class "Default")
      (node (ref "U$7") (pin "2") (pinfunction "VIN-_2") (pintype "input"))
    )
    (net (code "118") (name "unconnected-(U$8-NC-Pad5)") (class "Default")
      (node (ref "U$8") (pin "5") (pinfunction "NC_5") (pintype "no_connect"))
    )
    (net (code "119") (name "unconnected-(U$8-NC_2-Pad8)") (class "Default")
      (node (ref "U$8") (pin "8") (pinfunction "NC_2_8") (pintype "no_connect"))
    )
    (net (code "120") (name "unconnected-(U$8-NC_3-Pad1)") (class "Default")
      (node (ref "U$8") (pin "1") (pinfunction "NC_3_1") (pintype "no_connect"))
    )
    (net (code "121") (name "unconnected-(U$8-VIN+-Pad3)") (class "Default")
      (node (ref "U$8") (pin "3") (pinfunction "VIN+_3") (pintype "input"))
    )
    (net (code "122") (name "unconnected-(U$8-VIN--Pad2)") (class "Default")
      (node (ref "U$8") (pin "2") (pinfunction "VIN-_2") (pintype "input"))
    )
    (net (code "123") (name "unconnected-(U$9-NC-Pad5)") (class "Default")
      (node (ref "U$9") (pin "5") (pinfunction "NC_5") (pintype "no_connect"))
    )
    (net (code "124") (name "unconnected-(U$9-NC_2-Pad8)") (class "Default")
      (node (ref "U$9") (pin "8") (pinfunction "NC_2_8") (pintype "no_connect"))
    )
    (net (code "125") (name "unconnected-(U$9-NC_3-Pad1)") (class "Default")
      (node (ref "U$9") (pin "1") (pinfunction "NC_3_1") (pintype "no_connect"))
    )
    (net (code "126") (name "unconnected-(U$9-VIN+-Pad3)") (class "Default")
      (node (ref "U$9") (pin "3") (pinfunction "VIN+_3") (pintype "input"))
    )
    (net (code "127") (name "unconnected-(U$9-VIN--Pad2)") (class "Default")
      (node (ref "U$9") (pin "2") (pinfunction "VIN-_2") (pintype "input"))
    )
    (net (code "128") (name "unconnected-(U$10-NC-Pad5)") (class "Default")
      (node (ref "U$10") (pin "5") (pinfunction "NC_5") (pintype "no_connect"))
    )
    (net (code "129") (name "unconnected-(U$10-NC_2-Pad8)") (class "Default")
      (node (ref "U$10") (pin "8") (pinfunction "NC_2_8") (pintype "no_connect"))
    )
    (net (code "130") (name "unconnected-(U$10-NC_3-Pad1)") (class "Default")
      (node (ref "U$10") (pin "1") (pinfunction "NC_3_1") (pintype "no_connect"))
    )
    (net (code "131") (name "unconnected-(U$10-VIN+-Pad3)") (class "Default")
      (node (ref "U$10") (pin "3") (pinfunction "VIN+_3") (pintype "input"))
    )
    (net (code "132") (name "unconnected-(U$10-VIN--Pad2)") (class "Default")
      (node (ref "U$10") (pin "2") (pinfunction "VIN-_2") (pintype "input"))
    )
    (net (code "133") (name "unconnected-(U$11-NC-Pad5)") (class "Default")
      (node (ref "U$11") (pin "5") (pinfunction "NC_5") (pintype "no_connect"))
    )
    (net (code "134") (name "unconnected-(U$11-NC_2-Pad8)") (class "Default")
      (node (ref "U$11") (pin "8") (pinfunction "NC_2_8") (pintype "no_connect"))
    )
    (net (code "135") (name "unconnected-(U$11-NC_3-Pad1)") (class "Default")
      (node (ref "U$11") (pin "1") (pinfunction "NC_3_1") (pintype "no_connect"))
    )
    (net (code "136") (name "unconnected-(U$11-VIN+-Pad3)") (class "Default")
      (node (ref "U$11") (pin "3") (pinfunction "VIN+_3") (pintype "input"))
    )
    (net (code "137") (name "unconnected-(U$11-VIN--Pad2)") (class "Default")
      (node (ref "U$11") (pin "2") (pinfunction "VIN-_2") (pintype "input"))
    )
    (net (code "138") (name "unconnected-(U$12-NC-Pad5)") (class "Default")
      (node (ref "U$12") (pin "5") (pinfunction "NC_5") (pintype "no_connect"))
    )
    (net (code "139") (name "unconnected-(U$12-NC_2-Pad8)") (class "Default")
      (node (ref "U$12") (pin "8") (pinfunction "NC_2_8") (pintype "no_connect"))
    )
    (net (code "140") (name "unconnected-(U$12-NC_3-Pad1)") (class "Default")
      (node (ref "U$12") (pin "1") (pinfunction "NC_3_1") (pintype "no_connect"))
    )
    (net (code "141") (name "unconnected-(U$12-VIN+-Pad3)") (class "Default")
      (node (ref "U$12") (pin "3") (pinfunction "VIN+_3") (pintype "input"))
    )
    (net (code "142") (name "unconnected-(U$12-VIN--Pad2)") (class "Default")
      (node (ref "U$12") (pin "2") (pinfunction "VIN-_2") (pintype "input"))
    )
    (net (code "143") (name "unconnected-(U$13-NC-Pad5)") (class "Default")
      (node (ref "U$13") (pin "5") (pinfunction "NC_5") (pintype "no_connect"))
    )
    (net (code "144") (name "unconnected-(U$13-NC_2-Pad8)") (class "Default")
      (node (ref "U$13") (pin "8") (pinfunction "NC_2_8") (pintype "no_connect"))
    )
    (net (code "145") (name "unconnected-(U$13-NC_3-Pad1)") (class "Default")
      (node (ref "U$13") (pin "1") (pinfunction "NC_3_1") (pintype "no_connect"))
    )
    (net (code "146") (name "unconnected-(U$13-VIN+-Pad3)") (class "Default")
      (node (ref "U$13") (pin "3") (pinfunction "VIN+_3") (pintype "input"))
    )
    (net (code "147") (name "unconnected-(U$13-VIN--Pad2)") (class "Default")
      (node (ref "U$13") (pin "2") (pinfunction "VIN-_2") (pintype "input"))
    )
    (net (code "148") (name "unconnected-(U$14-NC-Pad5)") (class "Default")
      (node (ref "U$14") (pin "5") (pinfunction "NC_5") (pintype "no_connect"))
    )
    (net (code "149") (name "unconnected-(U$14-NC_2-Pad8)") (class "Default")
      (node (ref "U$14") (pin "8") (pinfunction "NC_2_8") (pintype "no_connect"))
    )
    (net (code "150") (name "unconnected-(U$14-NC_3-Pad1)") (class "Default")
      (node (ref "U$14") (pin "1") (pinfunction "NC_3_1") (pintype "no_connect"))
    )
    (net (code "151") (name "unconnected-(U$14-VIN+-Pad3)") (class "Default")
      (node (ref "U$14") (pin "3") (pinfunction "VIN+_3") (pintype "input"))
    )
    (net (code "152") (name "unconnected-(U$14-VIN--Pad2)") (class "Default")
      (node (ref "U$14") (pin "2") (pinfunction "VIN-_2") (pintype "input"))
    )
    (net (code "153") (name "unconnected-(U$15-NC-Pad5)") (class "Default")
      (node (ref "U$15") (pin "5") (pinfunction "NC_5") (pintype "no_connect"))
    )
    (net (code "154") (name "unconnected-(U$15-NC_2-Pad8)") (class "Default")
      (node (ref "U$15") (pin "8") (pinfunction "NC_2_8") (pintype "no_connect"))
    )
    (net (code "155") (name "unconnected-(U$15-NC_3-Pad1)") (class "Default")
      (node (ref "U$15") (pin "1") (pinfunction "NC_3_1") (pintype "no_connect"))
    )
    (net (code "156") (name "unconnected-(U$15-VIN+-Pad3)") (class "Default")
      (node (ref "U$15") (pin "3") (pinfunction "VIN+_3") (pintype "input"))
    )
    (net (code "157") (name "unconnected-(U$15-VIN--Pad2)") (class "Default")
      (node (ref "U$15") (pin "2") (pinfunction "VIN-_2") (pintype "input"))
    )
    (net (code "158") (name "unconnected-(U$16-NC-Pad5)") (class "Default")
      (node (ref "U$16") (pin "5") (pinfunction "NC_5") (pintype "no_connect"))
    )
    (net (code "159") (name "unconnected-(U$16-NC_2-Pad8)") (class "Default")
      (node (ref "U$16") (pin "8") (pinfunction "NC_2_8") (pintype "no_connect"))
    )
    (net (code "160") (name "unconnected-(U$16-NC_3-Pad1)") (class "Default")
      (node (ref "U$16") (pin "1") (pinfunction "NC_3_1") (pintype "no_connect"))
    )
    (net (code "161") (name "unconnected-(U$16-VIN+-Pad3)") (class "Default")
      (node (ref "U$16") (pin "3") (pinfunction "VIN+_3") (pintype "input"))
    )
    (net (code "162") (name "unconnected-(U$16-VIN--Pad2)") (class "Default")
      (node (ref "U$16") (pin "2") (pinfunction "VIN-_2") (pintype "input"))
    )
    (net (code "163") (name "unconnected-(U1-F0-Pad19)") (class "Default")
      (node (ref "U1") (pin "19") (pinfunction "F0_19") (pintype "input"))
    )
    (net (code "164") (name "unconnected-(U1-NC-Pad14)") (class "Default")
      (node (ref "U1") (pin "14") (pinfunction "NC_14") (pintype "no_connect"))
    )
    (net (code "165") (name "unconnected-(U1-NC_2-Pad13)") (class "Default")
      (node (ref "U1") (pin "13") (pinfunction "NC_2_13") (pintype "no_connect"))
    )
    (net (code "166") (name "unconnected-(U1-SCK-Pad18)") (class "Default")
      (node (ref "U1") (pin "18") (pinfunction "SCK_18") (pintype "bidirectional"))
    )
    (net (code "167") (name "unconnected-(U1-SDI-Pad20)") (class "Default")
      (node (ref "U1") (pin "20") (pinfunction "SDI_20") (pintype "input"))
    )
    (net (code "168") (name "unconnected-(U1-SDO-Pad17)") (class "Default")
      (node (ref "U1") (pin "17") (pinfunction "SDO_17") (pintype "output"))
    )
    (net (code "169") (name "unconnected-(U1-~{CS}-Pad16)") (class "Default")
      (node (ref "U1") (pin "16") (pinfunction "~{CS}_16") (pintype "input"))
    )
    (net (code "170") (name "unconnected-(U2-COMMON_IN{slash}OUT-Pad1)") (class "Default")
      (node (ref "U2") (pin "1") (pinfunction "COMMON_IN/OUT_1") (pintype "bidirectional"))
    )
    (net (code "171") (name "unconnected-(U2-S0-Pad10)") (class "Default")
      (node (ref "U2") (pin "10") (pinfunction "S0_10") (pintype "input"))
    )
    (net (code "172") (name "unconnected-(U2-S1-Pad11)") (class "Default")
      (node (ref "U2") (pin "11") (pinfunction "S1_11") (pintype "input"))
    )
    (net (code "173") (name "unconnected-(U2-S2-Pad14)") (class "Default")
      (node (ref "U2") (pin "14") (pinfunction "S2_14") (pintype "input"))
    )
    (net (code "174") (name "unconnected-(U2-S3-Pad13)") (class "Default")
      (node (ref "U2") (pin "13") (pinfunction "S3_13") (pintype "input"))
    )
    (net (code "175") (name "unconnected-(U2-~{E}-Pad15)") (class "Default")
      (node (ref "U2") (pin "15") (pinfunction "~{E}_15") (pintype "input"))
    )
    (net (code "176") (name "unconnected-(U3-COMMON_IN{slash}OUT-Pad1)") (class "Default")
      (node (ref "U3") (pin "1") (pinfunction "COMMON_IN/OUT_1") (pintype "bidirectional"))
    )
    (net (code "177") (name "unconnected-(U3-S0-Pad10)") (class "Default")
      (node (ref "U3") (pin "10") (pinfunction "S0_10") (pintype "input"))
    )
    (net (code "178") (name "unconnected-(U3-S1-Pad11)") (class "Default")
      (node (ref "U3") (pin "11") (pinfunction "S1_11") (pintype "input"))
    )
    (net (code "179") (name "unconnected-(U3-S2-Pad14)") (class "Default")
      (node (ref "U3") (pin "14") (pinfunction "S2_14") (pintype "input"))
    )
    (net (code "180") (name "unconnected-(U3-S3-Pad13)") (class "Default")
      (node (ref "U3") (pin "13") (pinfunction "S3_13") (pintype "input"))
    )
    (net (code "181") (name "unconnected-(U3-~{E}-Pad15)") (class "Default")
      (node (ref "U3") (pin "15") (pinfunction "~{E}_15") (pintype "input"))
    )
    (net (code "182") (name "unconnected-(U4-COMMON_IN{slash}OUT-Pad1)") (class "Default")
      (node (ref "U4") (pin "1") (pinfunction "COMMON_IN/OUT_1") (pintype "bidirectional"))
    )
    (net (code "183") (name "unconnected-(U4-S0-Pad10)") (class "Default")
      (node (ref "U4") (pin "10") (pinfunction "S0_10") (pintype "input"))
    )
    (net (code "184") (name "unconnected-(U4-S1-Pad11)") (class "Default")
      (node (ref "U4") (pin "11") (pinfunction "S1_11") (pintype "input"))
    )
    (net (code "185") (name "unconnected-(U4-S2-Pad14)") (class "Default")
      (node (ref "U4") (pin "14") (pinfunction "S2_14") (pintype "input"))
    )
    (net (code "186") (name "unconnected-(U4-S3-Pad13)") (class "Default")
      (node (ref "U4") (pin "13") (pinfunction "S3_13") (pintype "input"))
    )
    (net (code "187") (name "unconnected-(U4-~{E}-Pad15)") (class "Default")
      (node (ref "U4") (pin "15") (pinfunction "~{E}_15") (pintype "input"))
    )
    (net (code "188") (name "unconnected-(U5-COMMON_IN{slash}OUT-Pad1)") (class "Default")
      (node (ref "U5") (pin "1") (pinfunction "COMMON_IN/OUT_1") (pintype "bidirectional"))
    )
    (net (code "189") (name "unconnected-(U5-S0-Pad10)") (class "Default")
      (node (ref "U5") (pin "10") (pinfunction "S0_10") (pintype "input"))
    )
    (net (code "190") (name "unconnected-(U5-S1-Pad11)") (class "Default")
      (node (ref "U5") (pin "11") (pinfunction "S1_11") (pintype "input"))
    )
    (net (code "191") (name "unconnected-(U5-S2-Pad14)") (class "Default")
      (node (ref "U5") (pin "14") (pinfunction "S2_14") (pintype "input"))
    )
    (net (code "192") (name "unconnected-(U5-S3-Pad13)") (class "Default")
      (node (ref "U5") (pin "13") (pinfunction "S3_13") (pintype "input"))
    )
    (net (code "193") (name "unconnected-(U5-~{E}-Pad15)") (class "Default")
      (node (ref "U5") (pin "15") (pinfunction "~{E}_15") (pintype "input"))
    )
    (net (code "194") (name "unconnected-(X1-Pad1)") (class "Default")
      (node (ref "X1") (pin "1") (pinfunction "1_1") (pintype "passive"))
    )
    (net (code "195") (name "unconnected-(X1-Pad2)") (class "Default")
      (node (ref "X1") (pin "2") (pinfunction "2_2") (pintype "passive"))
    )
    (net (code "196") (name "unconnected-(X1-Pad3)") (class "Default")
      (node (ref "X1") (pin "3") (pinfunction "3_3") (pintype "passive"))
    )
    (net (code "197") (name "unconnected-(X1-Pad4)") (class "Default")
      (node (ref "X1") (pin "4") (pinfunction "4_4") (pintype "passive"))
    )
    (net (code "198") (name "unconnected-(X1-Pad5)") (class "Default")
      (node (ref "X1") (pin "5") (pinfunction "5_5") (pintype "passive"))
    )
    (net (code "199") (name "unconnected-(X1-Pad6)") (class "Default")
      (node (ref "X1") (pin "6") (pinfunction "6_6") (pintype "passive"))
    )
    (net (code "200") (name "unconnected-(X1-Pad7)") (class "Default")
      (node (ref "X1") (pin "7") (pinfunction "7_7") (pintype "passive"))
    )
    (net (code "201") (name "unconnected-(X1-Pad8)") (class "Default")
      (node (ref "X1") (pin "8") (pinfunction "8_8") (pintype "passive"))
    )
    (net (code "202") (name "unconnected-(X1-Pad9)") (class "Default")
      (node (ref "X1") (pin "9") (pinfunction "9_9") (pintype "passive"))
    )
    (net (code "203") (name "unconnected-(X1-Pad10)") (class "Default")
      (node (ref "X1") (pin "10") (pinfunction "10_10") (pintype "passive"))
    )
    (net (code "204") (name "unconnected-(X1-Pad11)") (class "Default")
      (node (ref "X1") (pin "11") (pinfunction "11_11") (pintype "passive"))
    )
    (net (code "205") (name "unconnected-(X1-Pad12)") (class "Default")
      (node (ref "X1") (pin "12") (pinfunction "12_12") (pintype "passive"))
    )
    (net (code "206") (name "unconnected-(X1-Pad13)") (class "Default")
      (node (ref "X1") (pin "13") (pinfunction "13_13") (pintype "passive"))
    )
    (net (code "207") (name "unconnected-(X1-Pad14)") (class "Default")
      (node (ref "X1") (pin "14") (pinfunction "14_14") (pintype "passive"))
    )
    (net (code "208") (name "unconnected-(X1-Pad15)") (class "Default")
      (node (ref "X1") (pin "15") (pinfunction "15_15") (pintype "passive"))
    )
    (net (code "209") (name "unconnected-(X1-Pad16)") (class "Default")
      (node (ref "X1") (pin "16") (pinfunction "16_16") (pintype "passive"))
    )
    (net (code "210") (name "unconnected-(X1-Pad17)") (class "Default")
      (node (ref "X1") (pin "17") (pinfunction "17_17") (pintype "passive"))
    )
    (net (code "211") (name "unconnected-(X1-Pad18)") (class "Default")
      (node (ref "X1") (pin "18") (pinfunction "18_18") (pintype "passive"))
    )
    (net (code "212") (name "unconnected-(X1-Pad19)") (class "Default")
      (node (ref "X1") (pin "19") (pinfunction "19_19") (pintype "passive"))
    )
    (net (code "213") (name "unconnected-(X1-Pad20)") (class "Default")
      (node (ref "X1") (pin "20") (pinfunction "20_20") (pintype "passive"))
    )
    (net (code "214") (name "unconnected-(X1-Pad21)") (class "Default")
      (node (ref "X1") (pin "21") (pinfunction "21_21") (pintype "passive"))
    )
    (net (code "215") (name "unconnected-(X1-Pad22)") (class "Default")
      (node (ref "X1") (pin "22") (pinfunction "22_22") (pintype "passive"))
    )
    (net (code "216") (name "unconnected-(X1-Pad23)") (class "Default")
      (node (ref "X1") (pin "23") (pinfunction "23_23") (pintype "passive"))
    )
    (net (code "217") (name "unconnected-(X1-Pad24)") (class "Default")
      (node (ref "X1") (pin "24") (pinfunction "24_24") (pintype "passive"))
    )
    (net (code "218") (name "unconnected-(X1-Pad25)") (class "Default")
      (node (ref "X1") (pin "25") (pinfunction "25_25") (pintype "passive"))
    )
    (net (code "219") (name "unconnected-(X1-Pad26)") (class "Default")
      (node (ref "X1") (pin "26") (pinfunction "26_26") (pintype "passive"))
    )
    (net (code "220") (name "unconnected-(X1-Pad27)") (class "Default")
      (node (ref "X1") (pin "27") (pinfunction "27_27") (pintype "passive"))
    )
    (net (code "221") (name "unconnected-(X1-Pad28)") (class "Default")
      (node (ref "X1") (pin "28") (pinfunction "28_28") (pintype "passive"))
    )
    (net (code "222") (name "unconnected-(X1-Pad29)") (class "Default")
      (node (ref "X1") (pin "29") (pinfunction "29_29") (pintype "passive"))
    )
    (net (code "223") (name "unconnected-(X1-Pad30)") (class "Default")
      (node (ref "X1") (pin "30") (pinfunction "30_30") (pintype "passive"))
    )
    (net (code "224") (name "unconnected-(X1-Pad31)") (class "Default")
      (node (ref "X1") (pin "31") (pinfunction "31_31") (pintype "passive"))
    )
    (net (code "225") (name "unconnected-(X1-Pad32)") (class "Default")
      (node (ref "X1") (pin "32") (pinfunction "32_32") (pintype "passive"))
    )
    (net (code "226") (name "unconnected-(X1-Pad33)") (class "Default")
      (node (ref "X1") (pin "33") (pinfunction "33_33") (pintype "passive"))
    )
    (net (code "227") (name "unconnected-(X1-Pad34)") (class "Default")
      (node (ref "X1") (pin "34") (pinfunction "34_34") (pintype "passive"))
    )
    (net (code "228") (name "unconnected-(X1-Pad35)") (class "Default")
      (node (ref "X1") (pin "35") (pinfunction "35_35") (pintype "passive"))
    )
    (net (code "229") (name "unconnected-(X1-Pad36)") (class "Default")
      (node (ref "X1") (pin "36") (pinfunction "36_36") (pintype "passive"))
    )
    (net (code "230") (name "unconnected-(X1-Pad37)") (class "Default")
      (node (ref "X1") (pin "37") (pinfunction "37_37") (pintype "passive"))
    )
    (net (code "231") (name "unconnected-(X1-Pad38)") (class "Default")
      (node (ref "X1") (pin "38") (pinfunction "38_38") (pintype "passive"))
    )
    (net (code "232") (name "unconnected-(X1-Pad39)") (class "Default")
      (node (ref "X1") (pin "39") (pinfunction "39_39") (pintype "passive"))
    )
    (net (code "233") (name "unconnected-(X1-Pad40)") (class "Default")
      (node (ref "X1") (pin "40") (pinfunction "40_40") (pintype "passive"))
    )
    (net (code "234") (name "unconnected-(X1-Pad41)") (class "Default")
      (node (ref "X1") (pin "41") (pinfunction "41_41") (pintype "passive"))
    )
    (net (code "235") (name "unconnected-(X1-Pad42)") (class "Default")
      (node (ref "X1") (pin "42") (pinfunction "42_42") (pintype "passive"))
    )
    (net (code "236") (name "unconnected-(X1-Pad43)") (class "Default")
      (node (ref "X1") (pin "43") (pinfunction "43_43") (pintype "passive"))
    )
    (net (code "237") (name "unconnected-(X1-Pad44)") (class "Default")
      (node (ref "X1") (pin "44") (pinfunction "44_44") (pintype "passive"))
    )
    (net (code "238") (name "unconnected-(X1-Pad45)") (class "Default")
      (node (ref "X1") (pin "45") (pinfunction "45_45") (pintype "passive"))
    )
    (net (code "239") (name "unconnected-(X1-Pad46)") (class "Default")
      (node (ref "X1") (pin "46") (pinfunction "46_46") (pintype "passive"))
    )
    (net (code "240") (name "unconnected-(X1-Pad47)") (class "Default")
      (node (ref "X1") (pin "47") (pinfunction "47_47") (pintype "passive"))
    )
    (net (code "241") (name "unconnected-(X1-Pad48)") (class "Default")
      (node (ref "X1") (pin "48") (pinfunction "48_48") (pintype "passive"))
    )
    (net (code "242") (name "unconnected-(X1-Pad49)") (class "Default")
      (node (ref "X1") (pin "49") (pinfunction "49_49") (pintype "passive"))
    )
    (net (code "243") (name "unconnected-(X1-Pad50)") (class "Default")
      (node (ref "X1") (pin "50") (pinfunction "50_50") (pintype "passive"))
    )
    (net (code "244") (name "unconnected-(X2-Pad33)") (class "Default")
      (node (ref "X2") (pin "33") (pinfunction "33_33") (pintype "passive"))
    )
    (net (code "245") (name "unconnected-(X2-Pad34)") (class "Default")
      (node (ref "X2") (pin "34") (pinfunction "34_34") (pintype "passive"))
    )
    (net (code "246") (name "unconnected-(X2-Pad35)") (class "Default")
      (node (ref "X2") (pin "35") (pinfunction "35_35") (pintype "passive"))
    )
    (net (code "247") (name "unconnected-(X2-Pad36)") (class "Default")
      (node (ref "X2") (pin "36") (pinfunction "36_36") (pintype "passive"))
    )
    (net (code "248") (name "unconnected-(X2-Pad37)") (class "Default")
      (node (ref "X2") (pin "37") (pinfunction "37_37") (pintype "passive"))
    )
    (net (code "249") (name "unconnected-(X2-Pad38)") (class "Default")
      (node (ref "X2") (pin "38") (pinfunction "38_38") (pintype "passive"))
    )
    (net (code "250") (name "unconnected-(X2-Pad39)") (class "Default")
      (node (ref "X2") (pin "39") (pinfunction "39_39") (pintype "passive"))
    )
    (net (code "251") (name "unconnected-(X2-Pad40)") (class "Default")
      (node (ref "X2") (pin "40") (pinfunction "40_40") (pintype "passive"))
    )
    (net (code "252") (name "unconnected-(X2-Pad41)") (class "Default")
      (node (ref "X2") (pin "41") (pinfunction "41_41") (pintype "passive"))
    )
    (net (code "253") (name "unconnected-(X2-Pad42)") (class "Default")
      (node (ref "X2") (pin "42") (pinfunction "42_42") (pintype "passive"))
    )
    (net (code "254") (name "unconnected-(X2-Pad43)") (class "Default")
      (node (ref "X2") (pin "43") (pinfunction "43_43") (pintype "passive"))
    )
    (net (code "255") (name "unconnected-(X2-Pad44)") (class "Default")
      (node (ref "X2") (pin "44") (pinfunction "44_44") (pintype "passive"))
    )
    (net (code "256") (name "unconnected-(X2-Pad45)") (class "Default")
      (node (ref "X2") (pin "45") (pinfunction "45_45") (pintype "passive"))
    )
    (net (code "257") (name "unconnected-(X2-Pad46)") (class "Default")
      (node (ref "X2") (pin "46") (pinfunction "46_46") (pintype "passive"))
    )
    (net (code "258") (name "unconnected-(X2-Pad47)") (class "Default")
      (node (ref "X2") (pin "47") (pinfunction "47_47") (pintype "passive"))
    )
    (net (code "259") (name "unconnected-(X2-Pad48)") (class "Default")
      (node (ref "X2") (pin "48") (pinfunction "48_48") (pintype "passive"))
    )
    (net (code "260") (name "unconnected-(X2-Pad49)") (class "Default")
      (node (ref "X2") (pin "49") (pinfunction "49_49") (pintype "passive"))
    )
    (net (code "261") (name "unconnected-(X2-Pad50)") (class "Default")
      (node (ref "X2") (pin "50") (pinfunction "50_50") (pintype "passive"))
    )
    (net (code "262") (name "unconnected-(X3-Pad33)") (class "Default")
      (node (ref "X3") (pin "33") (pinfunction "33_33") (pintype "passive"))
    )
    (net (code "263") (name "unconnected-(X3-Pad34)") (class "Default")
      (node (ref "X3") (pin "34") (pinfunction "34_34") (pintype "passive"))
    )
    (net (code "264") (name "unconnected-(X3-Pad35)") (class "Default")
      (node (ref "X3") (pin "35") (pinfunction "35_35") (pintype "passive"))
    )
    (net (code "265") (name "unconnected-(X3-Pad36)") (class "Default")
      (node (ref "X3") (pin "36") (pinfunction "36_36") (pintype "passive"))
    )
    (net (code "266") (name "unconnected-(X3-Pad37)") (class "Default")
      (node (ref "X3") (pin "37") (pinfunction "37_37") (pintype "passive"))
    )
    (net (code "267") (name "unconnected-(X3-Pad38)") (class "Default")
      (node (ref "X3") (pin "38") (pinfunction "38_38") (pintype "passive"))
    )
    (net (code "268") (name "unconnected-(X3-Pad39)") (class "Default")
      (node (ref "X3") (pin "39") (pinfunction "39_39") (pintype "passive"))
    )
    (net (code "269") (name "unconnected-(X3-Pad40)") (class "Default")
      (node (ref "X3") (pin "40") (pinfunction "40_40") (pintype "passive"))
    )
    (net (code "270") (name "unconnected-(X3-Pad41)") (class "Default")
      (node (ref "X3") (pin "41") (pinfunction "41_41") (pintype "passive"))
    )
    (net (code "271") (name "unconnected-(X3-Pad42)") (class "Default")
      (node (ref "X3") (pin "42") (pinfunction "42_42") (pintype "passive"))
    )
    (net (code "272") (name "unconnected-(X3-Pad43)") (class "Default")
      (node (ref "X3") (pin "43") (pinfunction "43_43") (pintype "passive"))
    )
    (net (code "273") (name "unconnected-(X3-Pad44)") (class "Default")
      (node (ref "X3") (pin "44") (pinfunction "44_44") (pintype "passive"))
    )
    (net (code "274") (name "unconnected-(X3-Pad45)") (class "Default")
      (node (ref "X3") (pin "45") (pinfunction "45_45") (pintype "passive"))
    )
    (net (code "275") (name "unconnected-(X3-Pad46)") (class "Default")
      (node (ref "X3") (pin "46") (pinfunction "46_46") (pintype "passive"))
    )
    (net (code "276") (name "unconnected-(X3-Pad47)") (class "Default")
      (node (ref "X3") (pin "47") (pinfunction "47_47") (pintype "passive"))
    )
    (net (code "277") (name "unconnected-(X3-Pad48)") (class "Default")
      (node (ref "X3") (pin "48") (pinfunction "48_48") (pintype "passive"))
    )
    (net (code "278") (name "unconnected-(X3-Pad49)") (class "Default")
      (node (ref "X3") (pin "49") (pinfunction "49_49") (pintype "passive"))
    )
    (net (code "279") (name "unconnected-(X3-Pad50)") (class "Default")
      (node (ref "X3") (pin "50") (pinfunction "50_50") (pintype "passive"))
    )
  )
)
